# rl_energy_board.net
KiCad netlist of a schematic drawn in EAGLE
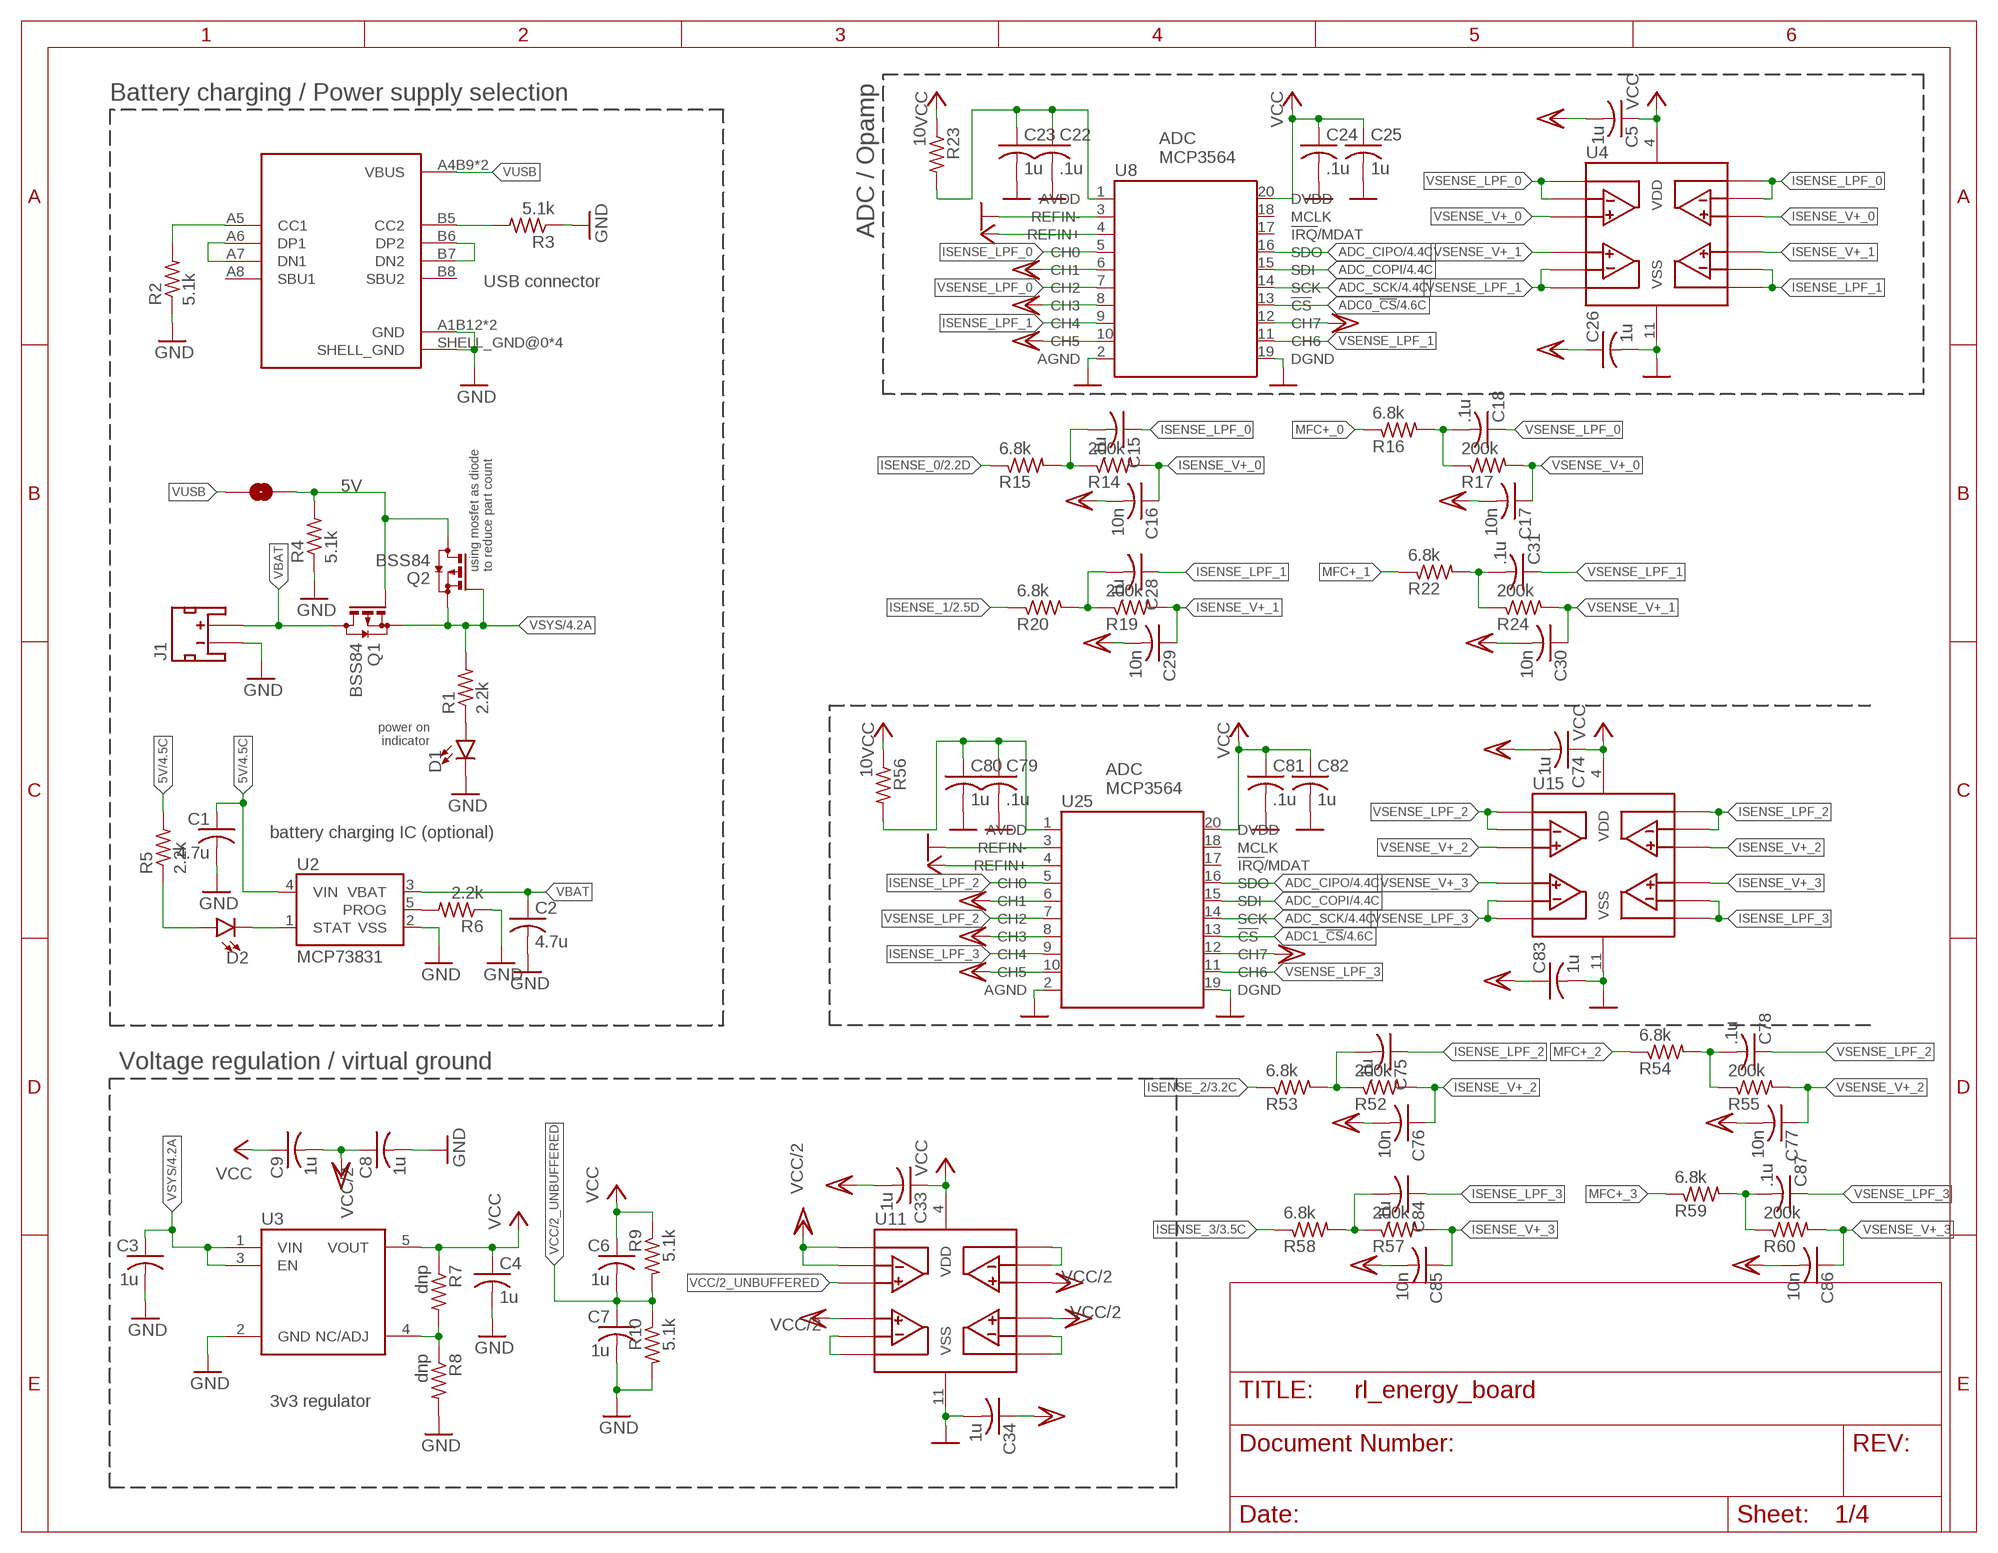
[diagram p0: schematic, sheet 1]
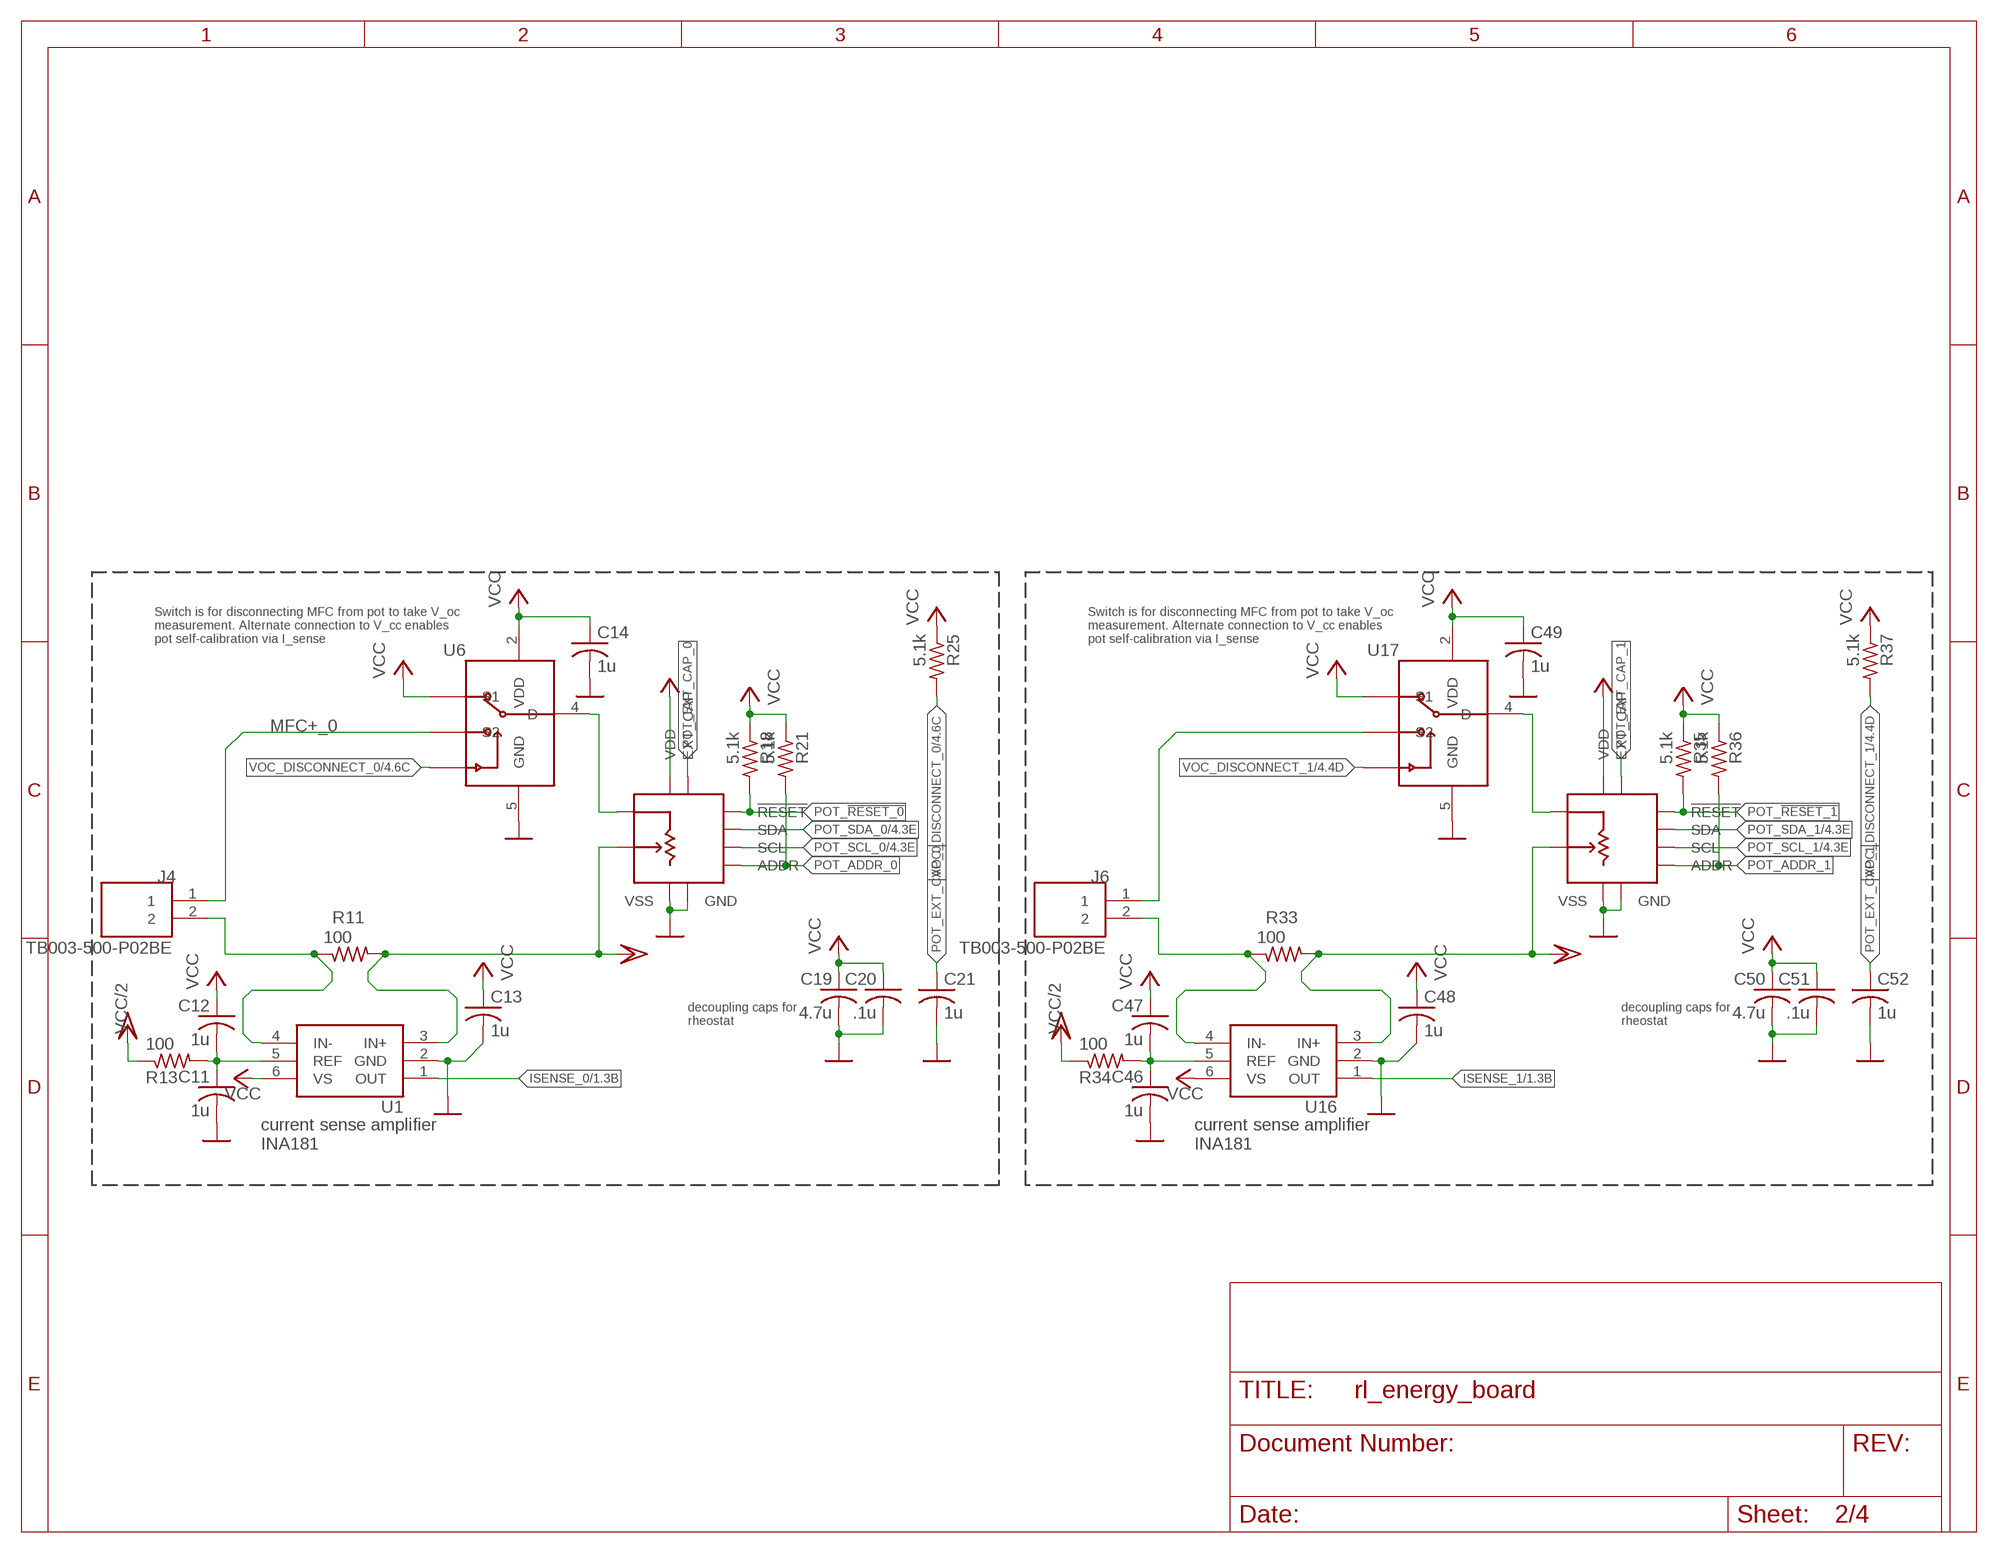
[diagram p1: schematic, sheet 2]
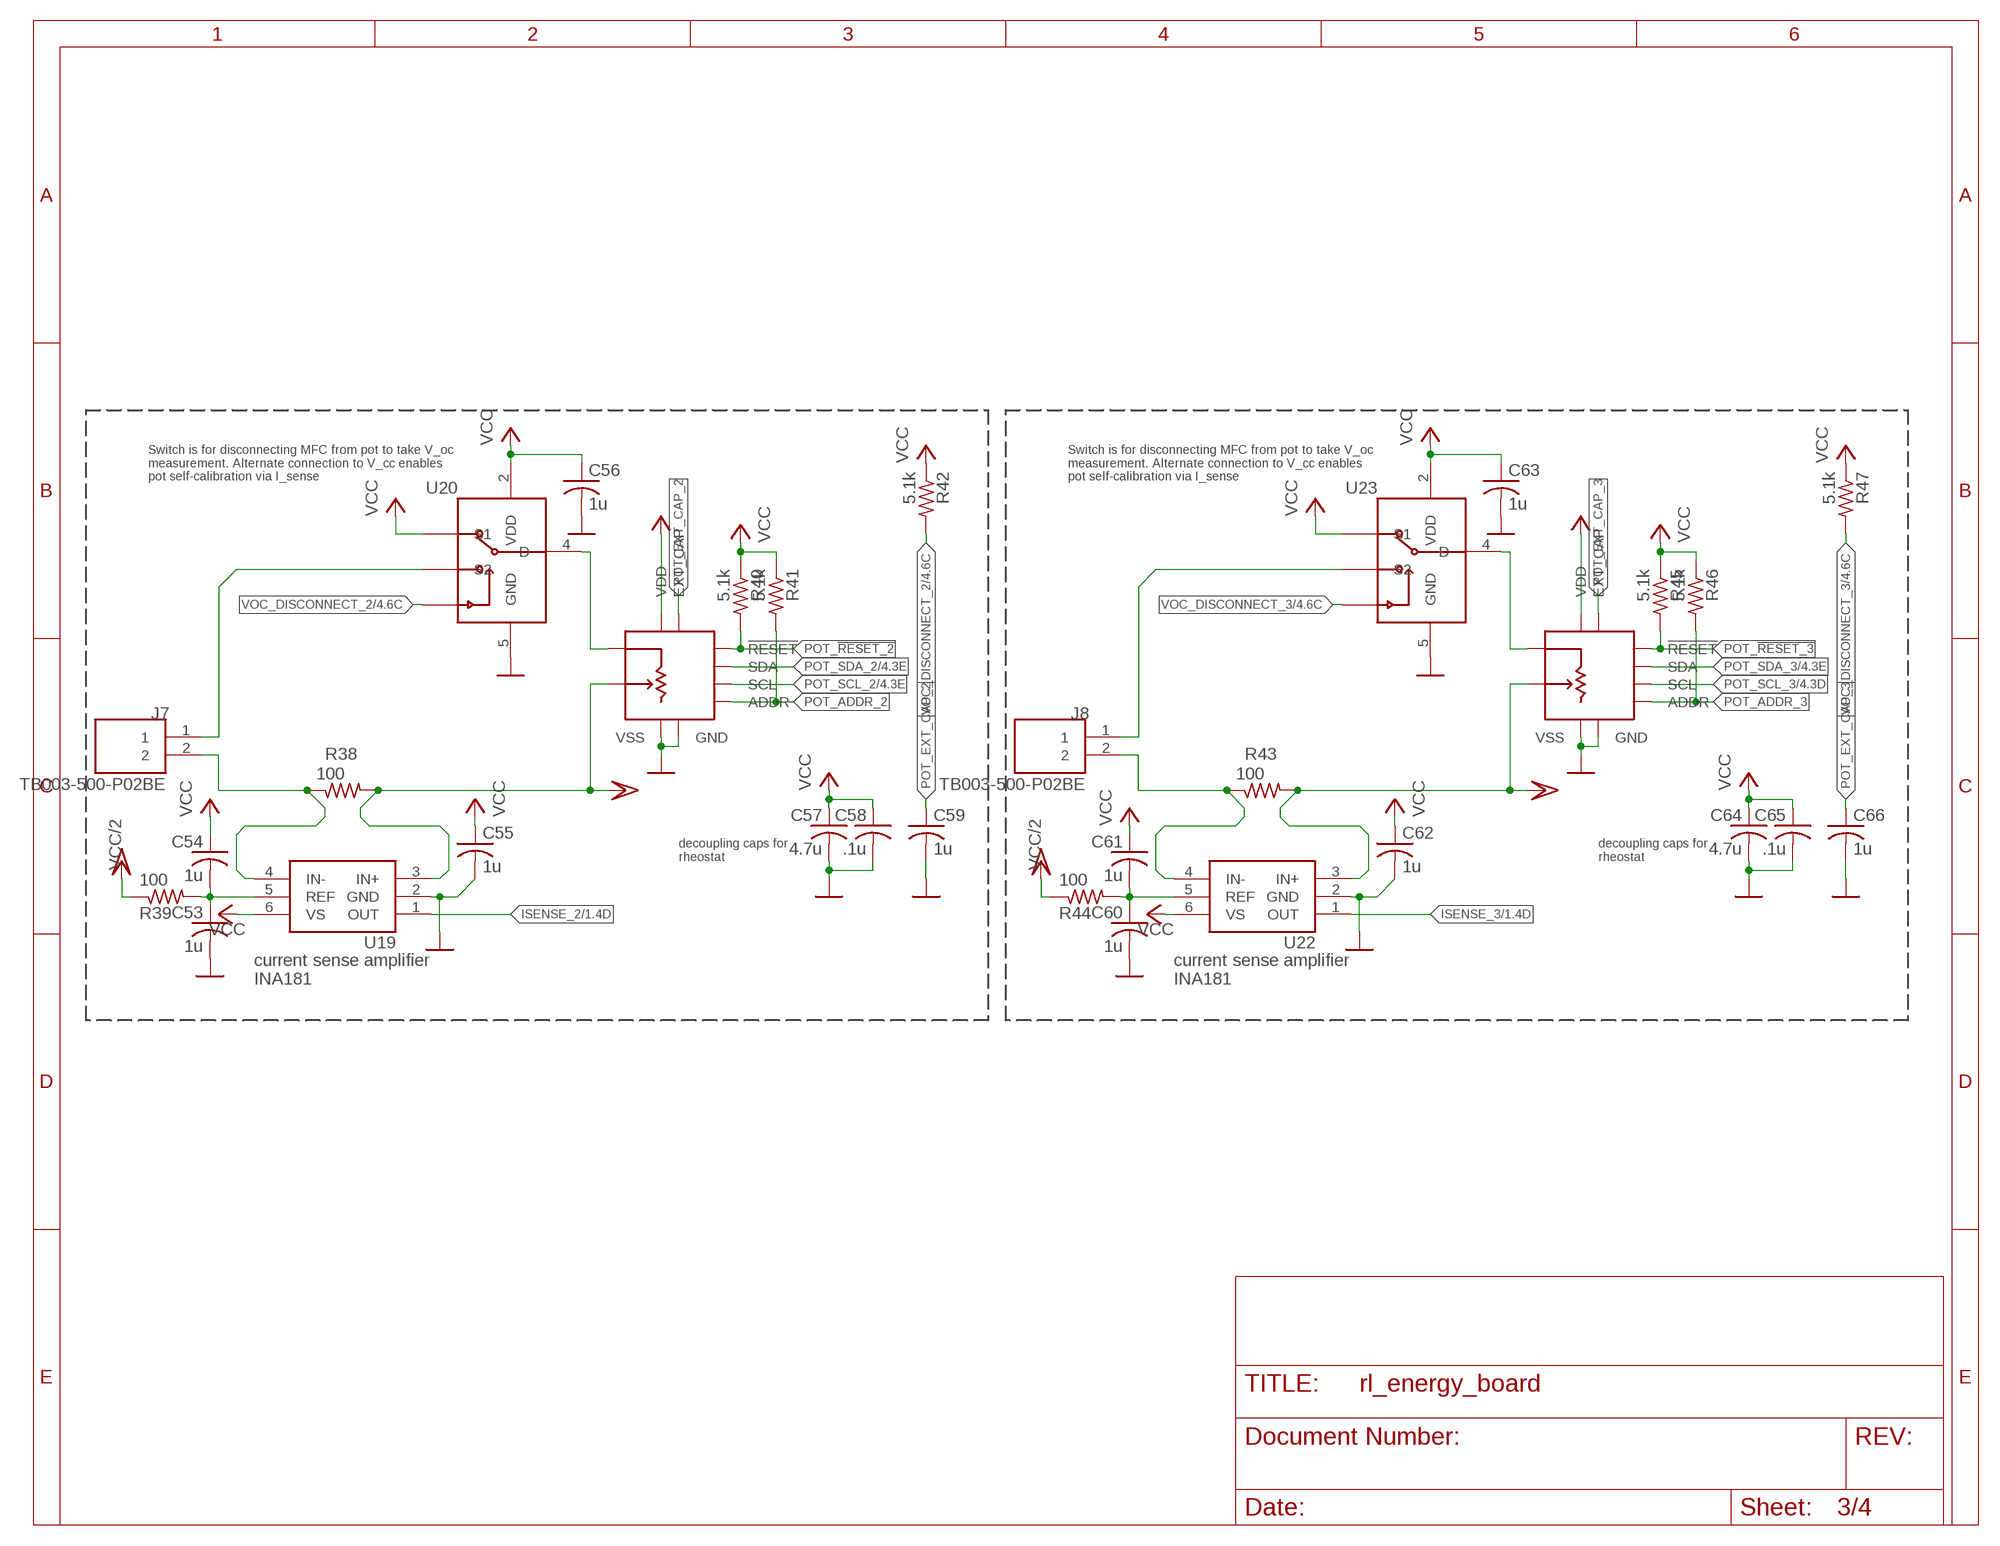
[diagram p2: schematic, sheet 3]
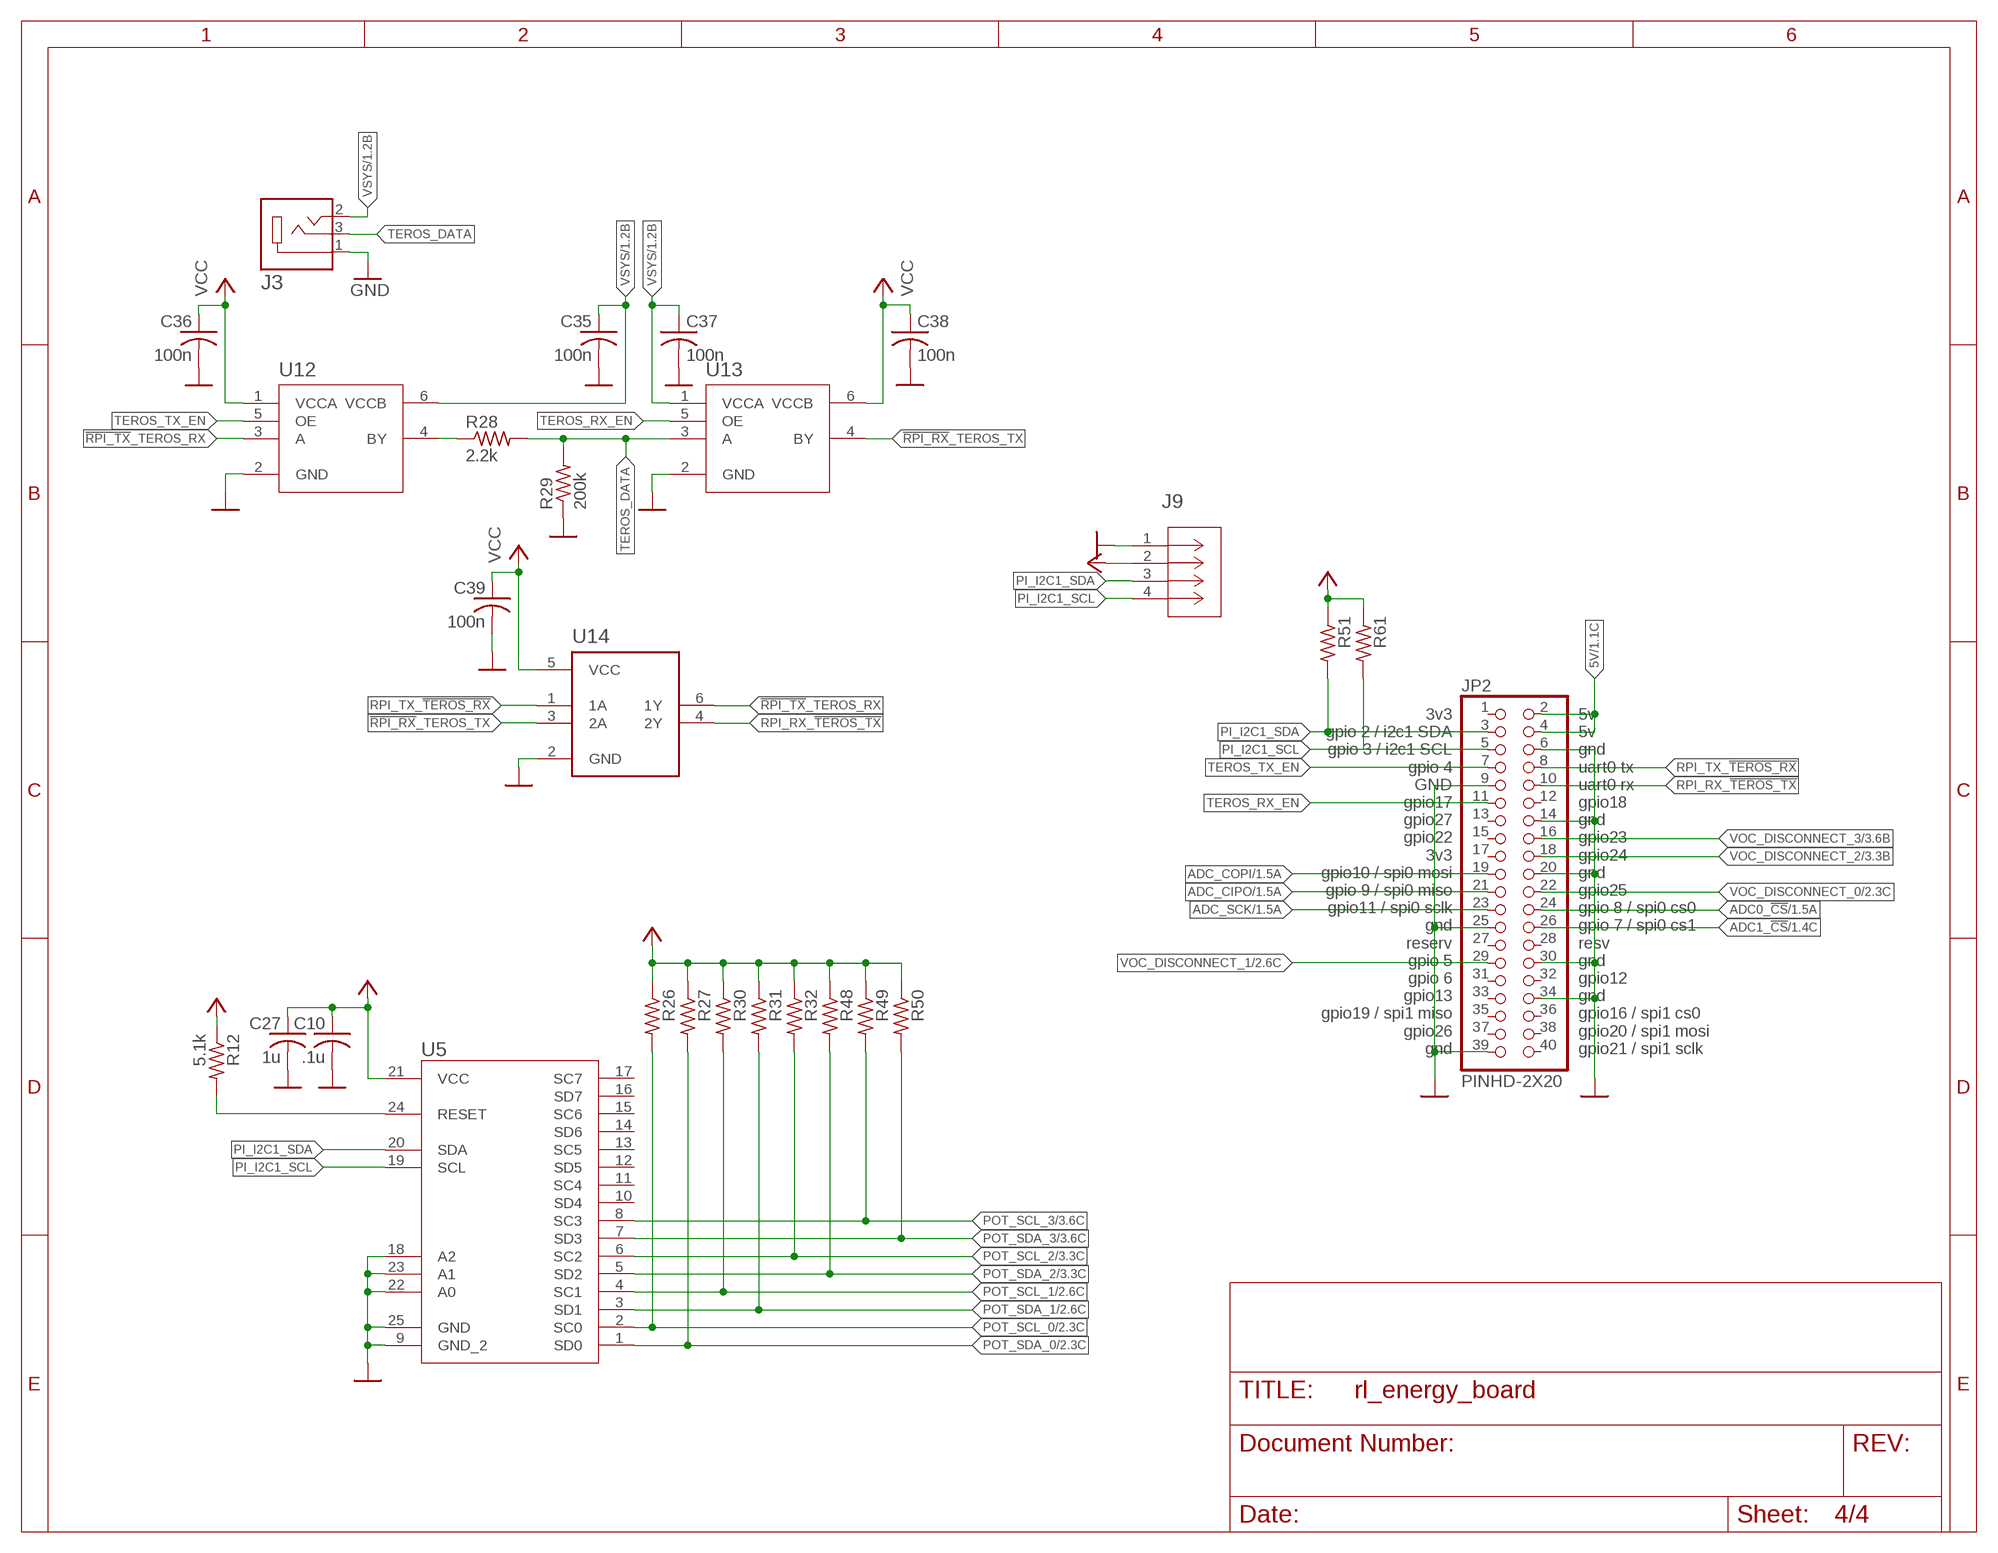
[diagram p3: schematic, sheet 4]

(export (version "E")
  (design (tool "Eeschema 10.0.6"))
  (components
    (comp (ref "C11")
      (value "1u")
      (footprint "eagle-import:C0402")
      (fields (field (name "MFR") "Samsung Electro-Mechanics"))
      (libsource (lib "eagle-import") (part "C-USC0402"))
    )
    (comp (ref "C12")
      (value "1u")
      (footprint "eagle-import:C0402")
      (fields (field (name "MFR") "Samsung Electro-Mechanics"))
      (libsource (lib "eagle-import") (part "C-USC0402"))
    )
    (comp (ref "C13")
      (value "1u")
      (footprint "eagle-import:C0402")
      (fields (field (name "MFR") "Samsung Electro-Mechanics"))
      (libsource (lib "eagle-import") (part "C-USC0402"))
    )
    (comp (ref "C14")
      (value "1u")
      (footprint "eagle-import:C0402")
      (fields (field (name "MFR") "Samsung Electro-Mechanics"))
      (libsource (lib "eagle-import") (part "C-USC0402"))
    )
    (comp (ref "C19")
      (value "4.7u")
      (footprint "eagle-import:C0603")
      (fields (field (name "MFR") "Samsung Electro-Mechanics"))
      (libsource (lib "eagle-import") (part "C-USC0603"))
    )
    (comp (ref "C20")
      (value ".1u")
      (footprint "eagle-import:C0402")
      (fields (field (name "MFR") "Samsung Electro-Mechanics"))
      (libsource (lib "eagle-import") (part "C-USC0402"))
    )
    (comp (ref "C21")
      (value "1u")
      (footprint "eagle-import:C0402")
      (fields (field (name "MFR") "Samsung Electro-Mechanics"))
      (libsource (lib "eagle-import") (part "C-USC0402"))
    )
    (comp (ref "C46")
      (value "1u")
      (footprint "eagle-import:C0402")
      (fields (field (name "MFR") "Samsung Electro-Mechanics"))
      (libsource (lib "eagle-import") (part "C-USC0402"))
    )
    (comp (ref "C47")
      (value "1u")
      (footprint "eagle-import:C0402")
      (fields (field (name "MFR") "Samsung Electro-Mechanics"))
      (libsource (lib "eagle-import") (part "C-USC0402"))
    )
    (comp (ref "C48")
      (value "1u")
      (footprint "eagle-import:C0402")
      (fields (field (name "MFR") "Samsung Electro-Mechanics"))
      (libsource (lib "eagle-import") (part "C-USC0402"))
    )
    (comp (ref "C49")
      (value "1u")
      (footprint "eagle-import:C0402")
      (fields (field (name "MFR") "Samsung Electro-Mechanics"))
      (libsource (lib "eagle-import") (part "C-USC0402"))
    )
    (comp (ref "C50")
      (value "4.7u")
      (footprint "eagle-import:C0603")
      (fields (field (name "MFR") "Samsung Electro-Mechanics"))
      (libsource (lib "eagle-import") (part "C-USC0603"))
    )
    (comp (ref "C51")
      (value ".1u")
      (footprint "eagle-import:C0402")
      (fields (field (name "MFR") "Samsung Electro-Mechanics"))
      (libsource (lib "eagle-import") (part "C-USC0402"))
    )
    (comp (ref "C52")
      (value "1u")
      (footprint "eagle-import:C0402")
      (fields (field (name "MFR") "Samsung Electro-Mechanics"))
      (libsource (lib "eagle-import") (part "C-USC0402"))
    )
    (comp (ref "J4")
      (value "TB003-500-P02BE")
      (footprint "eagle-import:CUI_TB003-500-P02BE")
      (fields (field (name "MANUFACTURER") "CUI"))
      (libsource (lib "eagle-import") (part "TB003-500-P02BE"))
    )
    (comp (ref "J6")
      (value "TB003-500-P02BE")
      (footprint "eagle-import:CUI_TB003-500-P02BE")
      (fields (field (name "MANUFACTURER") "CUI"))
      (libsource (lib "eagle-import") (part "TB003-500-P02BE"))
    )
    (comp (ref "R11")
      (value "100")
      (footprint "eagle-import:R0603")
      (fields (field (name "MFR") "Stackpole Electronics Incorporated"))
      (libsource (lib "eagle-import") (part "R-US_R0603"))
    )
    (comp (ref "R13")
      (value "100")
      (footprint "eagle-import:R0402")
      (fields (field (name "MFR") "Yageo"))
      (libsource (lib "eagle-import") (part "R-US_R0402"))
    )
    (comp (ref "R18")
      (value "5.1k")
      (footprint "eagle-import:R0402")
      (fields (field (name "MFR") "Yageo"))
      (libsource (lib "eagle-import") (part "R-US_R0402"))
    )
    (comp (ref "R21")
      (value "5.1k")
      (footprint "eagle-import:R0402")
      (fields (field (name "MFR") "Yageo"))
      (libsource (lib "eagle-import") (part "R-US_R0402"))
    )
    (comp (ref "R25")
      (value "5.1k")
      (footprint "eagle-import:R0402")
      (fields (field (name "MFR") "Yageo"))
      (libsource (lib "eagle-import") (part "R-US_R0402"))
    )
    (comp (ref "R33")
      (value "100")
      (footprint "eagle-import:R0603")
      (fields (field (name "MFR") "Stackpole Electronics Incorporated"))
      (libsource (lib "eagle-import") (part "R-US_R0603"))
    )
    (comp (ref "R34")
      (value "100")
      (footprint "eagle-import:R0402")
      (fields (field (name "MFR") "Yageo"))
      (libsource (lib "eagle-import") (part "R-US_R0402"))
    )
    (comp (ref "R35")
      (value "5.1k")
      (footprint "eagle-import:R0402")
      (fields (field (name "MFR") "Yageo"))
      (libsource (lib "eagle-import") (part "R-US_R0402"))
    )
    (comp (ref "R36")
      (value "5.1k")
      (footprint "eagle-import:R0402")
      (fields (field (name "MFR") "Yageo"))
      (libsource (lib "eagle-import") (part "R-US_R0402"))
    )
    (comp (ref "R37")
      (value "5.1k")
      (footprint "eagle-import:R0402")
      (fields (field (name "MFR") "Yageo"))
      (libsource (lib "eagle-import") (part "R-US_R0402"))
    )
    (comp (ref "U1")
      (value "INA181")
      (footprint "eagle-import:SOT95P280X145-6N")
      (fields (field (name "MFR") "Texas Instruments"))
      (libsource (lib "eagle-import") (part "INA181"))
    )
    (comp (ref "U6")
      (value "TMUX1247")
      (footprint "eagle-import:SOT65P210X110-6N")
      (fields (field (name "MFR") "Texas Instruments"))
      (libsource (lib "eagle-import") (part "TMUX1247"))
    )
    (comp (ref "U7")
      (value "AD5272BRMZ-XXX")
      (footprint "eagle-import:SOP50P490X95-10N")
      (fields (field (name "MFR") "Analog Devices"))
      (libsource (lib "eagle-import") (part "AD5272BRMZ-XXX"))
    )
    (comp (ref "U16")
      (value "INA181")
      (footprint "eagle-import:SOT95P280X145-6N")
      (fields (field (name "MFR") "Texas Instruments"))
      (libsource (lib "eagle-import") (part "INA181"))
    )
    (comp (ref "U17")
      (value "TMUX1247")
      (footprint "eagle-import:SOT65P210X110-6N")
      (fields (field (name "MFR") "Texas Instruments"))
      (libsource (lib "eagle-import") (part "TMUX1247"))
    )
    (comp (ref "U18")
      (value "AD5272BRMZ-XXX")
      (footprint "eagle-import:SOP50P490X95-10N")
      (fields (field (name "MFR") "Analog Devices"))
      (libsource (lib "eagle-import") (part "AD5272BRMZ-XXX"))
    )
    (comp (ref "C53")
      (value "1u")
      (footprint "eagle-import:C0402")
      (fields (field (name "MFR") "Samsung Electro-Mechanics"))
      (libsource (lib "eagle-import") (part "C-USC0402"))
    )
    (comp (ref "C54")
      (value "1u")
      (footprint "eagle-import:C0402")
      (fields (field (name "MFR") "Samsung Electro-Mechanics"))
      (libsource (lib "eagle-import") (part "C-USC0402"))
    )
    (comp (ref "C55")
      (value "1u")
      (footprint "eagle-import:C0402")
      (fields (field (name "MFR") "Samsung Electro-Mechanics"))
      (libsource (lib "eagle-import") (part "C-USC0402"))
    )
    (comp (ref "C56")
      (value "1u")
      (footprint "eagle-import:C0402")
      (fields (field (name "MFR") "Samsung Electro-Mechanics"))
      (libsource (lib "eagle-import") (part "C-USC0402"))
    )
    (comp (ref "C57")
      (value "4.7u")
      (footprint "eagle-import:C0603")
      (fields (field (name "MFR") "Samsung Electro-Mechanics"))
      (libsource (lib "eagle-import") (part "C-USC0603"))
    )
    (comp (ref "C58")
      (value ".1u")
      (footprint "eagle-import:C0402")
      (fields (field (name "MFR") "Samsung Electro-Mechanics"))
      (libsource (lib "eagle-import") (part "C-USC0402"))
    )
    (comp (ref "C59")
      (value "1u")
      (footprint "eagle-import:C0402")
      (fields (field (name "MFR") "Samsung Electro-Mechanics"))
      (libsource (lib "eagle-import") (part "C-USC0402"))
    )
    (comp (ref "C60")
      (value "1u")
      (footprint "eagle-import:C0402")
      (fields (field (name "MFR") "Samsung Electro-Mechanics"))
      (libsource (lib "eagle-import") (part "C-USC0402"))
    )
    (comp (ref "C61")
      (value "1u")
      (footprint "eagle-import:C0402")
      (fields (field (name "MFR") "Samsung Electro-Mechanics"))
      (libsource (lib "eagle-import") (part "C-USC0402"))
    )
    (comp (ref "C62")
      (value "1u")
      (footprint "eagle-import:C0402")
      (fields (field (name "MFR") "Samsung Electro-Mechanics"))
      (libsource (lib "eagle-import") (part "C-USC0402"))
    )
    (comp (ref "C63")
      (value "1u")
      (footprint "eagle-import:C0402")
      (fields (field (name "MFR") "Samsung Electro-Mechanics"))
      (libsource (lib "eagle-import") (part "C-USC0402"))
    )
    (comp (ref "C64")
      (value "4.7u")
      (footprint "eagle-import:C0603")
      (fields (field (name "MFR") "Samsung Electro-Mechanics"))
      (libsource (lib "eagle-import") (part "C-USC0603"))
    )
    (comp (ref "C65")
      (value ".1u")
      (footprint "eagle-import:C0402")
      (fields (field (name "MFR") "Samsung Electro-Mechanics"))
      (libsource (lib "eagle-import") (part "C-USC0402"))
    )
    (comp (ref "C66")
      (value "1u")
      (footprint "eagle-import:C0402")
      (fields (field (name "MFR") "Samsung Electro-Mechanics"))
      (libsource (lib "eagle-import") (part "C-USC0402"))
    )
    (comp (ref "J7")
      (value "TB003-500-P02BE")
      (footprint "eagle-import:CUI_TB003-500-P02BE")
      (fields (field (name "MANUFACTURER") "CUI"))
      (libsource (lib "eagle-import") (part "TB003-500-P02BE"))
    )
    (comp (ref "J8")
      (value "TB003-500-P02BE")
      (footprint "eagle-import:CUI_TB003-500-P02BE")
      (fields (field (name "MANUFACTURER") "CUI"))
      (libsource (lib "eagle-import") (part "TB003-500-P02BE"))
    )
    (comp (ref "R38")
      (value "100")
      (footprint "eagle-import:R0603")
      (fields (field (name "MFR") "Stackpole Electronics Incorporated"))
      (libsource (lib "eagle-import") (part "R-US_R0603"))
    )
    (comp (ref "R39")
      (value "100")
      (footprint "eagle-import:R0402")
      (fields (field (name "MFR") "Yageo"))
      (libsource (lib "eagle-import") (part "R-US_R0402"))
    )
    (comp (ref "R40")
      (value "5.1k")
      (footprint "eagle-import:R0402")
      (fields (field (name "MFR") "Yageo"))
      (libsource (lib "eagle-import") (part "R-US_R0402"))
    )
    (comp (ref "R41")
      (value "5.1k")
      (footprint "eagle-import:R0402")
      (fields (field (name "MFR") "Yageo"))
      (libsource (lib "eagle-import") (part "R-US_R0402"))
    )
    (comp (ref "R42")
      (value "5.1k")
      (footprint "eagle-import:R0402")
      (fields (field (name "MFR") "Yageo"))
      (libsource (lib "eagle-import") (part "R-US_R0402"))
    )
    (comp (ref "R43")
      (value "100")
      (footprint "eagle-import:R0603")
      (fields (field (name "MFR") "Stackpole Electronics Incorporated"))
      (libsource (lib "eagle-import") (part "R-US_R0603"))
    )
    (comp (ref "R44")
      (value "100")
      (footprint "eagle-import:R0402")
      (fields (field (name "MFR") "Yageo"))
      (libsource (lib "eagle-import") (part "R-US_R0402"))
    )
    (comp (ref "R45")
      (value "5.1k")
      (footprint "eagle-import:R0402")
      (fields (field (name "MFR") "Yageo"))
      (libsource (lib "eagle-import") (part "R-US_R0402"))
    )
    (comp (ref "R46")
      (value "5.1k")
      (footprint "eagle-import:R0402")
      (fields (field (name "MFR") "Yageo"))
      (libsource (lib "eagle-import") (part "R-US_R0402"))
    )
    (comp (ref "R47")
      (value "5.1k")
      (footprint "eagle-import:R0402")
      (fields (field (name "MFR") "Yageo"))
      (libsource (lib "eagle-import") (part "R-US_R0402"))
    )
    (comp (ref "U19")
      (value "INA181")
      (footprint "eagle-import:SOT95P280X145-6N")
      (fields (field (name "MFR") "Texas Instruments"))
      (libsource (lib "eagle-import") (part "INA181"))
    )
    (comp (ref "U20")
      (value "TMUX1247")
      (footprint "eagle-import:SOT65P210X110-6N")
      (fields (field (name "MFR") "Texas Instruments"))
      (libsource (lib "eagle-import") (part "TMUX1247"))
    )
    (comp (ref "U21")
      (value "AD5272BRMZ-XXX")
      (footprint "eagle-import:SOP50P490X95-10N")
      (fields (field (name "MFR") "Analog Devices"))
      (libsource (lib "eagle-import") (part "AD5272BRMZ-XXX"))
    )
    (comp (ref "U22")
      (value "INA181")
      (footprint "eagle-import:SOT95P280X145-6N")
      (fields (field (name "MFR") "Texas Instruments"))
      (libsource (lib "eagle-import") (part "INA181"))
    )
    (comp (ref "U23")
      (value "TMUX1247")
      (footprint "eagle-import:SOT65P210X110-6N")
      (fields (field (name "MFR") "Texas Instruments"))
      (libsource (lib "eagle-import") (part "TMUX1247"))
    )
    (comp (ref "U24")
      (value "AD5272BRMZ-XXX")
      (footprint "eagle-import:SOP50P490X95-10N")
      (fields (field (name "MFR") "Analog Devices"))
      (libsource (lib "eagle-import") (part "AD5272BRMZ-XXX"))
    )
    (comp (ref "C10")
      (value ".1u")
      (footprint "eagle-import:C0402")
      (fields (field (name "MFR") "Samsung Electro-Mechanics"))
      (libsource (lib "eagle-import") (part "C-USC0402"))
    )
    (comp (ref "C27")
      (value "1u")
      (footprint "eagle-import:C0402")
      (fields (field (name "MFR") "Samsung Electro-Mechanics"))
      (libsource (lib "eagle-import") (part "C-USC0402"))
    )
    (comp (ref "C35")
      (value "100n")
      (footprint "eagle-import:C0402")
      (libsource (lib "eagle-import") (part "C-USC0402"))
    )
    (comp (ref "C36")
      (value "100n")
      (footprint "eagle-import:C0402")
      (libsource (lib "eagle-import") (part "C-USC0402"))
    )
    (comp (ref "C37")
      (value "100n")
      (footprint "eagle-import:C0402")
      (libsource (lib "eagle-import") (part "C-USC0402"))
    )
    (comp (ref "C38")
      (value "100n")
      (footprint "eagle-import:C0402")
      (libsource (lib "eagle-import") (part "C-USC0402"))
    )
    (comp (ref "C39")
      (value "100n")
      (footprint "eagle-import:C0402")
      (libsource (lib "eagle-import") (part "C-USC0402"))
    )
    (comp (ref "J3")
      (value "SJ-3523-SMT-TR")
      (footprint "eagle-import:CUI_SJ-3523-SMT-TR")
      (fields (field (name "MF") "CUI Inc"))
      (libsource (lib "eagle-import") (part "SJ-3523-SMT-TR"))
    )
    (comp (ref "J9")
      (value "SM04B-SRSS-TB")
      (footprint "eagle-import:CONN_SM04B-SRSS-TB_JST")
      (fields (field (name "COPYRIGHT") "Copyright (C) 2024 Ultra Librarian. All rights reserved."))
      (libsource (lib "eagle-import") (part "SM04B-SRSS-TB"))
    )
    (comp (ref "JP2")
      (value "PINHD-2X20")
      (footprint "eagle-import:2X20")
      (libsource (lib "eagle-import") (part "PINHD-2X20"))
    )
    (comp (ref "R12")
      (value "5.1k")
      (footprint "eagle-import:R0402")
      (fields (field (name "MFR") "Yageo"))
      (libsource (lib "eagle-import") (part "R-US_R0402"))
    )
    (comp (ref "R26")
      (value "5.1k")
      (footprint "eagle-import:R0402")
      (fields (field (name "MFR") "Yageo"))
      (libsource (lib "eagle-import") (part "R-US_R0402"))
    )
    (comp (ref "R27")
      (value "5.1k")
      (footprint "eagle-import:R0402")
      (fields (field (name "MFR") "Yageo"))
      (libsource (lib "eagle-import") (part "R-US_R0402"))
    )
    (comp (ref "R28")
      (value "2.2k")
      (footprint "eagle-import:R0402")
      (libsource (lib "eagle-import") (part "R-US_R0402"))
    )
    (comp (ref "R29")
      (value "200k")
      (footprint "eagle-import:R0402")
      (libsource (lib "eagle-import") (part "R-US_R0402"))
    )
    (comp (ref "R30")
      (value "5.1k")
      (footprint "eagle-import:R0402")
      (fields (field (name "MFR") "Yageo"))
      (libsource (lib "eagle-import") (part "R-US_R0402"))
    )
    (comp (ref "R31")
      (value "5.1k")
      (footprint "eagle-import:R0402")
      (fields (field (name "MFR") "Yageo"))
      (libsource (lib "eagle-import") (part "R-US_R0402"))
    )
    (comp (ref "R32")
      (value "5.1k")
      (footprint "eagle-import:R0402")
      (fields (field (name "MFR") "Yageo"))
      (libsource (lib "eagle-import") (part "R-US_R0402"))
    )
    (comp (ref "R48")
      (value "5.1k")
      (footprint "eagle-import:R0402")
      (fields (field (name "MFR") "Yageo"))
      (libsource (lib "eagle-import") (part "R-US_R0402"))
    )
    (comp (ref "R49")
      (value "5.1k")
      (footprint "eagle-import:R0402")
      (fields (field (name "MFR") "Yageo"))
      (libsource (lib "eagle-import") (part "R-US_R0402"))
    )
    (comp (ref "R50")
      (value "5.1k")
      (footprint "eagle-import:R0402")
      (fields (field (name "MFR") "Yageo"))
      (libsource (lib "eagle-import") (part "R-US_R0402"))
    )
    (comp (ref "R51")
      (value "5.1k")
      (footprint "eagle-import:R0402")
      (fields (field (name "MFR") "Yageo"))
      (libsource (lib "eagle-import") (part "R-US_R0402"))
    )
    (comp (ref "R61")
      (value "5.1k")
      (footprint "eagle-import:R0402")
      (fields (field (name "MFR") "Yageo"))
      (libsource (lib "eagle-import") (part "R-US_R0402"))
    )
    (comp (ref "U5")
      (value "TCA9548ARGERQ1")
      (footprint "eagle-import:QFN_GERQ1_TEX")
      (fields (field (name "COPYRIGHT") "Copyright (C) 2024 Ultra Librarian. All rights reserved."))
      (libsource (lib "eagle-import") (part "TCA9548ARGERQ1"))
    )
    (comp (ref "U12")
      (value "TXU0101QDCKRQ1")
      (footprint "eagle-import:SOT_101QDCKRQ1_TEX")
      (fields (field (name "COPYRIGHT") "Copyright (C) 2024 Ultra Librarian. All rights reserved."))
      (libsource (lib "eagle-import") (part "TXU0101QDCKRQ1"))
    )
    (comp (ref "U13")
      (value "TXU0101QDCKRQ1")
      (footprint "eagle-import:SOT_101QDCKRQ1_TEX")
      (fields (field (name "COPYRIGHT") "Copyright (C) 2024 Ultra Librarian. All rights reserved."))
      (libsource (lib "eagle-import") (part "TXU0101QDCKRQ1"))
    )
    (comp (ref "U14")
      (value "SN74LVC2G14DCKR")
      (footprint "eagle-import:SOT65P210X110-6N")
      (libsource (lib "eagle-import") (part "SN74LVC2G14DCKR"))
    )
    (comp (ref "C1")
      (value "4.7u")
      (footprint "eagle-import:C0603")
      (fields (field (name "MFR") "Samsung Electro-Mechanics"))
      (libsource (lib "eagle-import") (part "C-USC0603"))
    )
    (comp (ref "C2")
      (value "4.7u")
      (footprint "eagle-import:C0603")
      (fields (field (name "MFR") "Samsung Electro-Mechanics"))
      (libsource (lib "eagle-import") (part "C-USC0603"))
    )
    (comp (ref "C3")
      (value "1u")
      (footprint "eagle-import:C0402")
      (fields (field (name "MFR") "Samsung Electro-Mechanics"))
      (libsource (lib "eagle-import") (part "C-USC0402"))
    )
    (comp (ref "C4")
      (value "1u")
      (footprint "eagle-import:C0402")
      (fields (field (name "MFR") "Samsung Electro-Mechanics"))
      (libsource (lib "eagle-import") (part "C-USC0402"))
    )
    (comp (ref "C5")
      (value "1u")
      (footprint "eagle-import:C0402")
      (fields (field (name "MFR") "Samsung Electro-Mechanics"))
      (libsource (lib "eagle-import") (part "C-USC0402"))
    )
    (comp (ref "C6")
      (value "1u")
      (footprint "eagle-import:C0402")
      (fields (field (name "MFR") "Samsung Electro-Mechanics"))
      (libsource (lib "eagle-import") (part "C-USC0402"))
    )
    (comp (ref "C7")
      (value "1u")
      (footprint "eagle-import:C0402")
      (fields (field (name "MFR") "Samsung Electro-Mechanics"))
      (libsource (lib "eagle-import") (part "C-USC0402"))
    )
    (comp (ref "C8")
      (value "1u")
      (footprint "eagle-import:C0402")
      (fields (field (name "MFR") "Samsung Electro-Mechanics"))
      (libsource (lib "eagle-import") (part "C-USC0402"))
    )
    (comp (ref "C9")
      (value "1u")
      (footprint "eagle-import:C0402")
      (fields (field (name "MFR") "Samsung Electro-Mechanics"))
      (libsource (lib "eagle-import") (part "C-USC0402"))
    )
    (comp (ref "C15")
      (value ".1u")
      (footprint "eagle-import:C0402")
      (fields (field (name "MFR") "Samsung Electro-Mechanics"))
      (libsource (lib "eagle-import") (part "C-USC0402"))
    )
    (comp (ref "C16")
      (value "10n")
      (footprint "eagle-import:C0402")
      (fields (field (name "MFR") "Samsung Electro-Mechanics"))
      (libsource (lib "eagle-import") (part "C-USC0402"))
    )
    (comp (ref "C17")
      (value "10n")
      (footprint "eagle-import:C0402")
      (fields (field (name "MFR") "Samsung Electro-Mechanics"))
      (libsource (lib "eagle-import") (part "C-USC0402"))
    )
    (comp (ref "C18")
      (value ".1u")
      (footprint "eagle-import:C0402")
      (fields (field (name "MFR") "Samsung Electro-Mechanics"))
      (libsource (lib "eagle-import") (part "C-USC0402"))
    )
    (comp (ref "C22")
      (value ".1u")
      (footprint "eagle-import:C0402")
      (fields (field (name "MFR") "Samsung Electro-Mechanics"))
      (libsource (lib "eagle-import") (part "C-USC0402"))
    )
    (comp (ref "C23")
      (value "1u")
      (footprint "eagle-import:C0402")
      (fields (field (name "MFR") "Samsung Electro-Mechanics"))
      (libsource (lib "eagle-import") (part "C-USC0402"))
    )
    (comp (ref "C24")
      (value ".1u")
      (footprint "eagle-import:C0402")
      (fields (field (name "MFR") "Samsung Electro-Mechanics"))
      (libsource (lib "eagle-import") (part "C-USC0402"))
    )
    (comp (ref "C25")
      (value "1u")
      (footprint "eagle-import:C0402")
      (fields (field (name "MFR") "Samsung Electro-Mechanics"))
      (libsource (lib "eagle-import") (part "C-USC0402"))
    )
    (comp (ref "C26")
      (value "1u")
      (footprint "eagle-import:C0402")
      (fields (field (name "MFR") "Samsung Electro-Mechanics"))
      (libsource (lib "eagle-import") (part "C-USC0402"))
    )
    (comp (ref "C28")
      (value ".1u")
      (footprint "eagle-import:C0402")
      (fields (field (name "MFR") "Samsung Electro-Mechanics"))
      (libsource (lib "eagle-import") (part "C-USC0402"))
    )
    (comp (ref "C29")
      (value "10n")
      (footprint "eagle-import:C0402")
      (fields (field (name "MFR") "Samsung Electro-Mechanics"))
      (libsource (lib "eagle-import") (part "C-USC0402"))
    )
    (comp (ref "C30")
      (value "10n")
      (footprint "eagle-import:C0402")
      (fields (field (name "MFR") "Samsung Electro-Mechanics"))
      (libsource (lib "eagle-import") (part "C-USC0402"))
    )
    (comp (ref "C31")
      (value ".1u")
      (footprint "eagle-import:C0402")
      (fields (field (name "MFR") "Samsung Electro-Mechanics"))
      (libsource (lib "eagle-import") (part "C-USC0402"))
    )
    (comp (ref "C33")
      (value "1u")
      (footprint "eagle-import:C0402")
      (fields (field (name "MFR") "Samsung Electro-Mechanics"))
      (libsource (lib "eagle-import") (part "C-USC0402"))
    )
    (comp (ref "C34")
      (value "1u")
      (footprint "eagle-import:C0402")
      (fields (field (name "MFR") "Samsung Electro-Mechanics"))
      (libsource (lib "eagle-import") (part "C-USC0402"))
    )
    (comp (ref "C74")
      (value "1u")
      (footprint "eagle-import:C0402")
      (fields (field (name "MFR") "Samsung Electro-Mechanics"))
      (libsource (lib "eagle-import") (part "C-USC0402"))
    )
    (comp (ref "C75")
      (value ".1u")
      (footprint "eagle-import:C0402")
      (fields (field (name "MFR") "Samsung Electro-Mechanics"))
      (libsource (lib "eagle-import") (part "C-USC0402"))
    )
    (comp (ref "C76")
      (value "10n")
      (footprint "eagle-import:C0402")
      (fields (field (name "MFR") "Samsung Electro-Mechanics"))
      (libsource (lib "eagle-import") (part "C-USC0402"))
    )
    (comp (ref "C77")
      (value "10n")
      (footprint "eagle-import:C0402")
      (fields (field (name "MFR") "Samsung Electro-Mechanics"))
      (libsource (lib "eagle-import") (part "C-USC0402"))
    )
    (comp (ref "C78")
      (value ".1u")
      (footprint "eagle-import:C0402")
      (fields (field (name "MFR") "Samsung Electro-Mechanics"))
      (libsource (lib "eagle-import") (part "C-USC0402"))
    )
    (comp (ref "C79")
      (value ".1u")
      (footprint "eagle-import:C0402")
      (fields (field (name "MFR") "Samsung Electro-Mechanics"))
      (libsource (lib "eagle-import") (part "C-USC0402"))
    )
    (comp (ref "C80")
      (value "1u")
      (footprint "eagle-import:C0402")
      (fields (field (name "MFR") "Samsung Electro-Mechanics"))
      (libsource (lib "eagle-import") (part "C-USC0402"))
    )
    (comp (ref "C81")
      (value ".1u")
      (footprint "eagle-import:C0402")
      (fields (field (name "MFR") "Samsung Electro-Mechanics"))
      (libsource (lib "eagle-import") (part "C-USC0402"))
    )
    (comp (ref "C82")
      (value "1u")
      (footprint "eagle-import:C0402")
      (fields (field (name "MFR") "Samsung Electro-Mechanics"))
      (libsource (lib "eagle-import") (part "C-USC0402"))
    )
    (comp (ref "C83")
      (value "1u")
      (footprint "eagle-import:C0402")
      (fields (field (name "MFR") "Samsung Electro-Mechanics"))
      (libsource (lib "eagle-import") (part "C-USC0402"))
    )
    (comp (ref "C84")
      (value ".1u")
      (footprint "eagle-import:C0402")
      (fields (field (name "MFR") "Samsung Electro-Mechanics"))
      (libsource (lib "eagle-import") (part "C-USC0402"))
    )
    (comp (ref "C85")
      (value "10n")
      (footprint "eagle-import:C0402")
      (fields (field (name "MFR") "Samsung Electro-Mechanics"))
      (libsource (lib "eagle-import") (part "C-USC0402"))
    )
    (comp (ref "C86")
      (value "10n")
      (footprint "eagle-import:C0402")
      (fields (field (name "MFR") "Samsung Electro-Mechanics"))
      (libsource (lib "eagle-import") (part "C-USC0402"))
    )
    (comp (ref "C87")
      (value ".1u")
      (footprint "eagle-import:C0402")
      (fields (field (name "MFR") "Samsung Electro-Mechanics"))
      (libsource (lib "eagle-import") (part "C-USC0402"))
    )
    (comp (ref "D1")
      (value "LED0603")
      (footprint "eagle-import:LED-0603")
      (fields (field (name "MFR") "Lite-On Incorporated"))
      (libsource (lib "eagle-import") (part "LED0603"))
    )
    (comp (ref "D2")
      (value "LED0603")
      (footprint "eagle-import:LED-0603")
      (fields (field (name "MFR") "Lite-On Incorporated"))
      (libsource (lib "eagle-import") (part "LED0603"))
    )
    (comp (ref "J1")
      (value "JST_2MM_MALE")
      (footprint "eagle-import:JST-2-SMD")
      (fields (field (name "MFR") "JST"))
      (libsource (lib "eagle-import") (part "JST_2MM_MALE"))
    )
    (comp (ref "J2")
      (value "USB4105")
      (footprint "eagle-import:USB4105")
      (fields (field (name "MFR") "GCT"))
      (libsource (lib "eagle-import") (part "USB4105"))
    )
    (comp (ref "JP1")
      (value "JUMPER-SMT_2_NO_NO-SILK")
      (footprint "eagle-import:SMT-JUMPER_2_NO_NO-SILK")
      (libsource (lib "eagle-import") (part "JUMPER-SMT_2_NO_NO-SILK"))
    )
    (comp (ref "Q1")
      (value "BSS84")
      (footprint "eagle-import:SOT23")
      (fields (field (name "MFR") "Taiwan Semiconductor Corporation"))
      (libsource (lib "eagle-import") (part "BSS84"))
    )
    (comp (ref "Q2")
      (value "BSS84")
      (footprint "eagle-import:SOT23")
      (fields (field (name "MFR") "Taiwan Semiconductor Corporation"))
      (libsource (lib "eagle-import") (part "BSS84"))
    )
    (comp (ref "R1")
      (value "2.2k")
      (footprint "eagle-import:R0402")
      (fields (field (name "MFR") "Yageo"))
      (libsource (lib "eagle-import") (part "resistor_348_R-US_R0402"))
    )
    (comp (ref "R2")
      (value "5.1k")
      (footprint "eagle-import:R0402")
      (fields (field (name "MFR") "Yageo"))
      (libsource (lib "eagle-import") (part "resistor_348_R-US_R0402"))
    )
    (comp (ref "R3")
      (value "5.1k")
      (footprint "eagle-import:R0402")
      (fields (field (name "MFR") "Yageo"))
      (libsource (lib "eagle-import") (part "resistor_348_R-US_R0402"))
    )
    (comp (ref "R4")
      (value "5.1k")
      (footprint "eagle-import:R0402")
      (fields (field (name "MFR") "Yageo"))
      (libsource (lib "eagle-import") (part "resistor_348_R-US_R0402"))
    )
    (comp (ref "R5")
      (value "2.2k")
      (footprint "eagle-import:R0402")
      (fields (field (name "MFR") "Yageo"))
      (libsource (lib "eagle-import") (part "resistor_348_R-US_R0402"))
    )
    (comp (ref "R6")
      (value "2.2k")
      (footprint "eagle-import:R0402")
      (fields (field (name "MFR") "Yageo"))
      (libsource (lib "eagle-import") (part "resistor_348_R-US_R0402"))
    )
    (comp (ref "R7")
      (value "dnp")
      (footprint "eagle-import:R0402")
      (libsource (lib "eagle-import") (part "resistor_348_R-US_R0402"))
    )
    (comp (ref "R8")
      (value "dnp")
      (footprint "eagle-import:R0402")
      (libsource (lib "eagle-import") (part "resistor_348_R-US_R0402"))
    )
    (comp (ref "R9")
      (value "5.1k")
      (footprint "eagle-import:R0402")
      (fields (field (name "MFR") "Yageo"))
      (libsource (lib "eagle-import") (part "resistor_348_R-US_R0402"))
    )
    (comp (ref "R10")
      (value "5.1k")
      (footprint "eagle-import:R0402")
      (fields (field (name "MFR") "Yageo"))
      (libsource (lib "eagle-import") (part "resistor_348_R-US_R0402"))
    )
    (comp (ref "R14")
      (value "200k")
      (footprint "eagle-import:R0402")
      (fields (field (name "MFR") "Yageo"))
      (libsource (lib "eagle-import") (part "R-US_R0402"))
    )
    (comp (ref "R15")
      (value "6.8k")
      (footprint "eagle-import:R0402")
      (fields (field (name "MFR") "Yageo"))
      (libsource (lib "eagle-import") (part "R-US_R0402"))
    )
    (comp (ref "R16")
      (value "6.8k")
      (footprint "eagle-import:R0402")
      (fields (field (name "MFR") "Yageo"))
      (libsource (lib "eagle-import") (part "R-US_R0402"))
    )
    (comp (ref "R17")
      (value "200k")
      (footprint "eagle-import:R0402")
      (fields (field (name "MFR") "Yageo"))
      (libsource (lib "eagle-import") (part "R-US_R0402"))
    )
    (comp (ref "R19")
      (value "200k")
      (footprint "eagle-import:R0402")
      (fields (field (name "MFR") "Yageo"))
      (libsource (lib "eagle-import") (part "R-US_R0402"))
    )
    (comp (ref "R20")
      (value "6.8k")
      (footprint "eagle-import:R0402")
      (fields (field (name "MFR") "Yageo"))
      (libsource (lib "eagle-import") (part "R-US_R0402"))
    )
    (comp (ref "R22")
      (value "6.8k")
      (footprint "eagle-import:R0402")
      (fields (field (name "MFR") "Yageo"))
      (libsource (lib "eagle-import") (part "R-US_R0402"))
    )
    (comp (ref "R23")
      (value "10")
      (footprint "eagle-import:R0402")
      (fields (field (name "MFR") "Stackpole Electronics Incorporated"))
      (libsource (lib "eagle-import") (part "R-US_R0402"))
    )
    (comp (ref "R24")
      (value "200k")
      (footprint "eagle-import:R0402")
      (fields (field (name "MFR") "Yageo"))
      (libsource (lib "eagle-import") (part "R-US_R0402"))
    )
    (comp (ref "R52")
      (value "200k")
      (footprint "eagle-import:R0402")
      (fields (field (name "MFR") "Yageo"))
      (libsource (lib "eagle-import") (part "R-US_R0402"))
    )
    (comp (ref "R53")
      (value "6.8k")
      (footprint "eagle-import:R0402")
      (fields (field (name "MFR") "Yageo"))
      (libsource (lib "eagle-import") (part "R-US_R0402"))
    )
    (comp (ref "R54")
      (value "6.8k")
      (footprint "eagle-import:R0402")
      (fields (field (name "MFR") "Yageo"))
      (libsource (lib "eagle-import") (part "R-US_R0402"))
    )
    (comp (ref "R55")
      (value "200k")
      (footprint "eagle-import:R0402")
      (fields (field (name "MFR") "Yageo"))
      (libsource (lib "eagle-import") (part "R-US_R0402"))
    )
    (comp (ref "R56")
      (value "10")
      (footprint "eagle-import:R0402")
      (fields (field (name "MFR") "Stackpole Electronics Incorporated"))
      (libsource (lib "eagle-import") (part "R-US_R0402"))
    )
    (comp (ref "R57")
      (value "200k")
      (footprint "eagle-import:R0402")
      (fields (field (name "MFR") "Yageo"))
      (libsource (lib "eagle-import") (part "R-US_R0402"))
    )
    (comp (ref "R58")
      (value "6.8k")
      (footprint "eagle-import:R0402")
      (fields (field (name "MFR") "Yageo"))
      (libsource (lib "eagle-import") (part "R-US_R0402"))
    )
    (comp (ref "R59")
      (value "6.8k")
      (footprint "eagle-import:R0402")
      (fields (field (name "MFR") "Yageo"))
      (libsource (lib "eagle-import") (part "R-US_R0402"))
    )
    (comp (ref "R60")
      (value "200k")
      (footprint "eagle-import:R0402")
      (fields (field (name "MFR") "Yageo"))
      (libsource (lib "eagle-import") (part "R-US_R0402"))
    )
    (comp (ref "U2")
      (value "MCP73831")
      (footprint "eagle-import:SOT23-5")
      (fields (field (name "MFR") "Microchip Technology"))
      (libsource (lib "eagle-import") (part "MCP73831"))
    )
    (comp (ref "U3")
      (value "AP7366")
      (footprint "eagle-import:SOT95P285X130-5N")
      (fields (field (name "MFR") "Diodes Incorporated"))
      (libsource (lib "eagle-import") (part "AP7366"))
    )
    (comp (ref "U4")
      (value "MCP6074")
      (footprint "eagle-import:SOP65P640X120-14N")
      (fields (field (name "MFR") "Microchip Technology"))
      (libsource (lib "eagle-import") (part "MCP6074"))
    )
    (comp (ref "U8")
      (value "MCP3564")
      (footprint "eagle-import:SOP65P640X120-20N")
      (fields (field (name "MFR") "Microchip Technology"))
      (libsource (lib "eagle-import") (part "MCP3564"))
    )
    (comp (ref "U11")
      (value "MCP6074")
      (footprint "eagle-import:SOP65P640X120-14N")
      (fields (field (name "MFR") "Microchip Technology"))
      (libsource (lib "eagle-import") (part "MCP6074"))
    )
    (comp (ref "U15")
      (value "MCP6074")
      (footprint "eagle-import:SOP65P640X120-14N")
      (fields (field (name "MFR") "Microchip Technology"))
      (libsource (lib "eagle-import") (part "MCP6074"))
    )
    (comp (ref "U25")
      (value "MCP3564")
      (footprint "eagle-import:SOP65P640X120-20N")
      (fields (field (name "MFR") "Microchip Technology"))
      (libsource (lib "eagle-import") (part "MCP3564"))
    )
  )
  (nets
    (net (code "1") (name "5V") (class "Default")
      (node (ref "C1") (pin "1") (pinfunction "1_1") (pintype "passive"))
      (node (ref "JP1") (pin "1") (pinfunction "1_1") (pintype "passive"))
      (node (ref "JP2") (pin "2") (pinfunction "2_2") (pintype "passive"))
      (node (ref "JP2") (pin "4") (pinfunction "4_4") (pintype "passive"))
      (node (ref "Q1") (pin "1") (pinfunction "G_1") (pintype "passive"))
      (node (ref "Q2") (pin "3") (pinfunction "D_3") (pintype "passive"))
      (node (ref "R4") (pin "2") (pinfunction "2_2") (pintype "passive"))
      (node (ref "R5") (pin "2") (pinfunction "2_2") (pintype "passive"))
      (node (ref "U2") (pin "4") (pinfunction "VIN_4") (pintype "power_in"))
    )
    (net (code "2") (name "ADC0_~{CS}") (class "Default")
      (node (ref "JP2") (pin "24") (pinfunction "24_24") (pintype "passive"))
      (node (ref "U8") (pin "13") (pinfunction "~{CS}_13") (pintype "bidirectional"))
    )
    (net (code "3") (name "ADC1_~{CS}") (class "Default")
      (node (ref "JP2") (pin "26") (pinfunction "26_26") (pintype "passive"))
      (node (ref "U25") (pin "13") (pinfunction "~{CS}_13") (pintype "bidirectional"))
    )
    (net (code "4") (name "ADC_CIPO") (class "Default")
      (node (ref "JP2") (pin "21") (pinfunction "21_21") (pintype "passive"))
      (node (ref "U25") (pin "16") (pinfunction "SDO_16") (pintype "bidirectional"))
      (node (ref "U8") (pin "16") (pinfunction "SDO_16") (pintype "bidirectional"))
    )
    (net (code "5") (name "ADC_COPI") (class "Default")
      (node (ref "JP2") (pin "19") (pinfunction "19_19") (pintype "passive"))
      (node (ref "U25") (pin "15") (pinfunction "SDI_15") (pintype "bidirectional"))
      (node (ref "U8") (pin "15") (pinfunction "SDI_15") (pintype "bidirectional"))
    )
    (net (code "6") (name "ADC_SCK") (class "Default")
      (node (ref "JP2") (pin "23") (pinfunction "23_23") (pintype "passive"))
      (node (ref "U25") (pin "14") (pinfunction "SCK_14") (pintype "bidirectional"))
      (node (ref "U8") (pin "14") (pinfunction "SCK_14") (pintype "bidirectional"))
    )
    (net (code "7") (name "GND") (class "Default")
      (node (ref "C1") (pin "2") (pinfunction "2_2") (pintype "passive"))
      (node (ref "C10") (pin "2") (pinfunction "2_2") (pintype "passive"))
      (node (ref "C11") (pin "2") (pinfunction "2_2") (pintype "passive"))
      (node (ref "C13") (pin "2") (pinfunction "2_2") (pintype "passive"))
      (node (ref "C14") (pin "2") (pinfunction "2_2") (pintype "passive"))
      (node (ref "C19") (pin "2") (pinfunction "2_2") (pintype "passive"))
      (node (ref "C2") (pin "2") (pinfunction "2_2") (pintype "passive"))
      (node (ref "C20") (pin "2") (pinfunction "2_2") (pintype "passive"))
      (node (ref "C21") (pin "2") (pinfunction "2_2") (pintype "passive"))
      (node (ref "C22") (pin "2") (pinfunction "2_2") (pintype "passive"))
      (node (ref "C23") (pin "2") (pinfunction "2_2") (pintype "passive"))
      (node (ref "C24") (pin "2") (pinfunction "2_2") (pintype "passive"))
      (node (ref "C25") (pin "2") (pinfunction "2_2") (pintype "passive"))
      (node (ref "C26") (pin "2") (pinfunction "2_2") (pintype "passive"))
      (node (ref "C27") (pin "2") (pinfunction "2_2") (pintype "passive"))
      (node (ref "C3") (pin "2") (pinfunction "2_2") (pintype "passive"))
      (node (ref "C34") (pin "2") (pinfunction "2_2") (pintype "passive"))
      (node (ref "C35") (pin "2") (pinfunction "2_2") (pintype "passive"))
      (node (ref "C36") (pin "2") (pinfunction "2_2") (pintype "passive"))
      (node (ref "C37") (pin "2") (pinfunction "2_2") (pintype "passive"))
      (node (ref "C38") (pin "2") (pinfunction "2_2") (pintype "passive"))
      (node (ref "C39") (pin "2") (pinfunction "2_2") (pintype "passive"))
      (node (ref "C4") (pin "2") (pinfunction "2_2") (pintype "passive"))
      (node (ref "C46") (pin "2") (pinfunction "2_2") (pintype "passive"))
      (node (ref "C48") (pin "2") (pinfunction "2_2") (pintype "passive"))
      (node (ref "C49") (pin "2") (pinfunction "2_2") (pintype "passive"))
      (node (ref "C50") (pin "2") (pinfunction "2_2") (pintype "passive"))
      (node (ref "C51") (pin "2") (pinfunction "2_2") (pintype "passive"))
      (node (ref "C52") (pin "2") (pinfunction "2_2") (pintype "passive"))
      (node (ref "C53") (pin "2") (pinfunction "2_2") (pintype "passive"))
      (node (ref "C55") (pin "2") (pinfunction "2_2") (pintype "passive"))
      (node (ref "C56") (pin "2") (pinfunction "2_2") (pintype "passive"))
      (node (ref "C57") (pin "2") (pinfunction "2_2") (pintype "passive"))
      (node (ref "C58") (pin "2") (pinfunction "2_2") (pintype "passive"))
      (node (ref "C59") (pin "2") (pinfunction "2_2") (pintype "passive"))
      (node (ref "C60") (pin "2") (pinfunction "2_2") (pintype "passive"))
      (node (ref "C62") (pin "2") (pinfunction "2_2") (pintype "passive"))
      (node (ref "C63") (pin "2") (pinfunction "2_2") (pintype "passive"))
      (node (ref "C64") (pin "2") (pinfunction "2_2") (pintype "passive"))
      (node (ref "C65") (pin "2") (pinfunction "2_2") (pintype "passive"))
      (node (ref "C66") (pin "2") (pinfunction "2_2") (pintype "passive"))
      (node (ref "C7") (pin "2") (pinfunction "2_2") (pintype "passive"))
      (node (ref "C79") (pin "2") (pinfunction "2_2") (pintype "passive"))
      (node (ref "C8") (pin "2") (pinfunction "2_2") (pintype "passive"))
      (node (ref "C80") (pin "2") (pinfunction "2_2") (pintype "passive"))
      (node (ref "C81") (pin "2") (pinfunction "2_2") (pintype "passive"))
      (node (ref "C82") (pin "2") (pinfunction "2_2") (pintype "passive"))
      (node (ref "C83") (pin "2") (pinfunction "2_2") (pintype "passive"))
      (node (ref "D1") (pin "C") (pinfunction "C_C") (pintype "passive"))
      (node (ref "J1") (pin "1") (pinfunction "-_1") (pintype "bidirectional"))
      (node (ref "J2") (pin "A1B12") (pinfunction "GND_A1B12") (pintype "bidirectional"))
      (node (ref "J2") (pin "B1A12") (pinfunction "GND_B1A12") (pintype "bidirectional"))
      (node (ref "J2") (pin "SHELL_GND@0") (pinfunction "SHELL_GND_SHELL_GND@0") (pintype "bidirectional"))
      (node (ref "J2") (pin "SHELL_GND@1") (pinfunction "SHELL_GND_SHELL_GND@1") (pintype "bidirectional"))
      (node (ref "J2") (pin "SHELL_GND@2") (pinfunction "SHELL_GND_SHELL_GND@2") (pintype "bidirectional"))
      (node (ref "J2") (pin "SHELL_GND@3") (pinfunction "SHELL_GND_SHELL_GND@3") (pintype "bidirectional"))
      (node (ref "J3") (pin "1") (pinfunction "1_1") (pintype "passive"))
      (node (ref "J9") (pin "1") (pinfunction "1_1") (pintype "passive"))
      (node (ref "JP2") (pin "14") (pinfunction "14_14") (pintype "passive"))
      (node (ref "JP2") (pin "20") (pinfunction "20_20") (pintype "passive"))
      (node (ref "JP2") (pin "25") (pinfunction "25_25") (pintype "passive"))
      (node (ref "JP2") (pin "30") (pinfunction "30_30") (pintype "passive"))
      (node (ref "JP2") (pin "34") (pinfunction "34_34") (pintype "passive"))
      (node (ref "JP2") (pin "39") (pinfunction "39_39") (pintype "passive"))
      (node (ref "JP2") (pin "6") (pinfunction "6_6") (pintype "passive"))
      (node (ref "JP2") (pin "9") (pinfunction "9_9") (pintype "passive"))
      (node (ref "R10") (pin "2") (pinfunction "2_2") (pintype "passive"))
      (node (ref "R2") (pin "1") (pinfunction "1_1") (pintype "passive"))
      (node (ref "R29") (pin "1") (pinfunction "1_1") (pintype "passive"))
      (node (ref "R3") (pin "1") (pinfunction "1_1") (pintype "passive"))
      (node (ref "R4") (pin "1") (pinfunction "1_1") (pintype "passive"))
      (node (ref "R6") (pin "1") (pinfunction "1_1") (pintype "passive"))
      (node (ref "R8") (pin "2") (pinfunction "2_2") (pintype "passive"))
      (node (ref "U1") (pin "2") (pinfunction "GND_2") (pintype "bidirectional"))
      (node (ref "U11") (pin "11") (pinfunction "VSS_11") (pintype "bidirectional"))
      (node (ref "U12") (pin "2") (pinfunction "GND_2") (pintype "passive"))
      (node (ref "U13") (pin "2") (pinfunction "GND_2") (pintype "passive"))
      (node (ref "U14") (pin "2") (pinfunction "GND_2") (pintype "power_in"))
      (node (ref "U15") (pin "11") (pinfunction "VSS_11") (pintype "bidirectional"))
      (node (ref "U16") (pin "2") (pinfunction "GND_2") (pintype "bidirectional"))
      (node (ref "U17") (pin "5") (pinfunction "GND_5") (pintype "bidirectional"))
      (node (ref "U18") (pin "4") (pinfunction "VSS_4") (pintype "bidirectional"))
      (node (ref "U18") (pin "6") (pinfunction "GND_6") (pintype "bidirectional"))
      (node (ref "U19") (pin "2") (pinfunction "GND_2") (pintype "bidirectional"))
      (node (ref "U2") (pin "2") (pinfunction "VSS_2") (pintype "power_in"))
      (node (ref "U20") (pin "5") (pinfunction "GND_5") (pintype "bidirectional"))
      (node (ref "U21") (pin "4") (pinfunction "VSS_4") (pintype "bidirectional"))
      (node (ref "U21") (pin "6") (pinfunction "GND_6") (pintype "bidirectional"))
      (node (ref "U22") (pin "2") (pinfunction "GND_2") (pintype "bidirectional"))
      (node (ref "U23") (pin "5") (pinfunction "GND_5") (pintype "bidirectional"))
      (node (ref "U24") (pin "4") (pinfunction "VSS_4") (pintype "bidirectional"))
      (node (ref "U24") (pin "6") (pinfunction "GND_6") (pintype "bidirectional"))
      (node (ref "U25") (pin "19") (pinfunction "DGND_19") (pintype "bidirectional"))
      (node (ref "U25") (pin "2") (pinfunction "AGND_2") (pintype "bidirectional"))
      (node (ref "U25") (pin "3") (pinfunction "REFIN-_3") (pintype "bidirectional"))
      (node (ref "U3") (pin "2") (pinfunction "GND_2") (pintype "bidirectional"))
      (node (ref "U4") (pin "11") (pinfunction "VSS_11") (pintype "bidirectional"))
      (node (ref "U5") (pin "18") (pinfunction "A2_18") (pintype "bidirectional"))
      (node (ref "U5") (pin "22") (pinfunction "A0_22") (pintype "bidirectional"))
      (node (ref "U5") (pin "23") (pinfunction "A1_23") (pintype "bidirectional"))
      (node (ref "U5") (pin "25") (pinfunction "GND_25") (pintype "passive"))
      (node (ref "U5") (pin "9") (pinfunction "GND_2_9") (pintype "passive"))
      (node (ref "U6") (pin "5") (pinfunction "GND_5") (pintype "bidirectional"))
      (node (ref "U7") (pin "4") (pinfunction "VSS_4") (pintype "bidirectional"))
      (node (ref "U7") (pin "6") (pinfunction "GND_6") (pintype "bidirectional"))
      (node (ref "U8") (pin "19") (pinfunction "DGND_19") (pintype "bidirectional"))
      (node (ref "U8") (pin "2") (pinfunction "AGND_2") (pintype "bidirectional"))
      (node (ref "U8") (pin "3") (pinfunction "REFIN-_3") (pintype "bidirectional"))
    )
    (net (code "8") (name "ISENSE_0") (class "Default")
      (node (ref "R15") (pin "1") (pinfunction "1_1") (pintype "passive"))
      (node (ref "U1") (pin "1") (pinfunction "OUT_1") (pintype "bidirectional"))
    )
    (net (code "9") (name "ISENSE_1") (class "Default")
      (node (ref "R20") (pin "1") (pinfunction "1_1") (pintype "passive"))
      (node (ref "U16") (pin "1") (pinfunction "OUT_1") (pintype "bidirectional"))
    )
    (net (code "10") (name "ISENSE_2") (class "Default")
      (node (ref "R53") (pin "1") (pinfunction "1_1") (pintype "passive"))
      (node (ref "U19") (pin "1") (pinfunction "OUT_1") (pintype "bidirectional"))
    )
    (net (code "11") (name "ISENSE_3") (class "Default")
      (node (ref "R58") (pin "1") (pinfunction "1_1") (pintype "passive"))
      (node (ref "U22") (pin "1") (pinfunction "OUT_1") (pintype "bidirectional"))
    )
    (net (code "12") (name "ISENSE_LPF_0") (class "Default")
      (node (ref "C15") (pin "1") (pinfunction "1_1") (pintype "passive"))
      (node (ref "U4") (pin "13") (pinfunction "P$13_13") (pintype "bidirectional"))
      (node (ref "U4") (pin "14") (pinfunction "P$14_14") (pintype "bidirectional"))
      (node (ref "U8") (pin "5") (pinfunction "CH0_5") (pintype "bidirectional"))
    )
    (net (code "13") (name "ISENSE_LPF_1") (class "Default")
      (node (ref "C28") (pin "1") (pinfunction "1_1") (pintype "passive"))
      (node (ref "U4") (pin "8") (pinfunction "P$8_8") (pintype "bidirectional"))
      (node (ref "U4") (pin "9") (pinfunction "P$9_9") (pintype "bidirectional"))
      (node (ref "U8") (pin "9") (pinfunction "CH4_9") (pintype "bidirectional"))
    )
    (net (code "14") (name "ISENSE_LPF_2") (class "Default")
      (node (ref "C75") (pin "1") (pinfunction "1_1") (pintype "passive"))
      (node (ref "U15") (pin "13") (pinfunction "P$13_13") (pintype "bidirectional"))
      (node (ref "U15") (pin "14") (pinfunction "P$14_14") (pintype "bidirectional"))
      (node (ref "U25") (pin "5") (pinfunction "CH0_5") (pintype "bidirectional"))
    )
    (net (code "15") (name "ISENSE_LPF_3") (class "Default")
      (node (ref "C84") (pin "1") (pinfunction "1_1") (pintype "passive"))
      (node (ref "U15") (pin "8") (pinfunction "P$8_8") (pintype "bidirectional"))
      (node (ref "U15") (pin "9") (pinfunction "P$9_9") (pintype "bidirectional"))
      (node (ref "U25") (pin "9") (pinfunction "CH4_9") (pintype "bidirectional"))
    )
    (net (code "16") (name "ISENSE_V+_0") (class "Default")
      (node (ref "C16") (pin "1") (pinfunction "1_1") (pintype "passive"))
      (node (ref "R14") (pin "2") (pinfunction "2_2") (pintype "passive"))
      (node (ref "U4") (pin "12") (pinfunction "P$12_12") (pintype "bidirectional"))
    )
    (net (code "17") (name "ISENSE_V+_1") (class "Default")
      (node (ref "C29") (pin "1") (pinfunction "1_1") (pintype "passive"))
      (node (ref "R19") (pin "2") (pinfunction "2_2") (pintype "passive"))
      (node (ref "U4") (pin "10") (pinfunction "P$10_10") (pintype "bidirectional"))
    )
    (net (code "18") (name "ISENSE_V+_2") (class "Default")
      (node (ref "C76") (pin "1") (pinfunction "1_1") (pintype "passive"))
      (node (ref "R52") (pin "2") (pinfunction "2_2") (pintype "passive"))
      (node (ref "U15") (pin "12") (pinfunction "P$12_12") (pintype "bidirectional"))
    )
    (net (code "19") (name "ISENSE_V+_3") (class "Default")
      (node (ref "C85") (pin "1") (pinfunction "1_1") (pintype "passive"))
      (node (ref "R57") (pin "2") (pinfunction "2_2") (pintype "passive"))
      (node (ref "U15") (pin "10") (pinfunction "P$10_10") (pintype "bidirectional"))
    )
    (net (code "20") (name "MFC+_0") (class "Default")
      (node (ref "J4") (pin "1") (pinfunction "1_1") (pintype "passive"))
      (node (ref "R16") (pin "1") (pinfunction "1_1") (pintype "passive"))
      (node (ref "U6") (pin "1") (pinfunction "S2_1") (pintype "bidirectional"))
    )
    (net (code "21") (name "MFC+_1") (class "Default")
      (node (ref "J6") (pin "1") (pinfunction "1_1") (pintype "passive"))
      (node (ref "R22") (pin "1") (pinfunction "1_1") (pintype "passive"))
      (node (ref "U17") (pin "1") (pinfunction "S2_1") (pintype "bidirectional"))
    )
    (net (code "22") (name "MFC+_2") (class "Default")
      (node (ref "J7") (pin "1") (pinfunction "1_1") (pintype "passive"))
      (node (ref "R54") (pin "1") (pinfunction "1_1") (pintype "passive"))
      (node (ref "U20") (pin "1") (pinfunction "S2_1") (pintype "bidirectional"))
    )
    (net (code "23") (name "MFC+_3") (class "Default")
      (node (ref "J8") (pin "1") (pinfunction "1_1") (pintype "passive"))
      (node (ref "R59") (pin "1") (pinfunction "1_1") (pintype "passive"))
      (node (ref "U23") (pin "1") (pinfunction "S2_1") (pintype "bidirectional"))
    )
    (net (code "24") (name "N$35") (class "Default")
      (node (ref "C78") (pin "2") (pinfunction "2_2") (pintype "passive"))
      (node (ref "R54") (pin "2") (pinfunction "2_2") (pintype "passive"))
      (node (ref "R55") (pin "1") (pinfunction "1_1") (pintype "passive"))
    )
    (net (code "25") (name "Net-(C15-Pad2)") (class "Default")
      (node (ref "C15") (pin "2") (pinfunction "2_2") (pintype "passive"))
      (node (ref "R14") (pin "1") (pinfunction "1_1") (pintype "passive"))
      (node (ref "R15") (pin "2") (pinfunction "2_2") (pintype "passive"))
    )
    (net (code "26") (name "Net-(C18-Pad2)") (class "Default")
      (node (ref "C18") (pin "2") (pinfunction "2_2") (pintype "passive"))
      (node (ref "R16") (pin "2") (pinfunction "2_2") (pintype "passive"))
      (node (ref "R17") (pin "1") (pinfunction "1_1") (pintype "passive"))
    )
    (net (code "27") (name "Net-(C28-Pad2)") (class "Default")
      (node (ref "C28") (pin "2") (pinfunction "2_2") (pintype "passive"))
      (node (ref "R19") (pin "1") (pinfunction "1_1") (pintype "passive"))
      (node (ref "R20") (pin "2") (pinfunction "2_2") (pintype "passive"))
    )
    (net (code "28") (name "Net-(C31-Pad2)") (class "Default")
      (node (ref "C31") (pin "2") (pinfunction "2_2") (pintype "passive"))
      (node (ref "R22") (pin "2") (pinfunction "2_2") (pintype "passive"))
      (node (ref "R24") (pin "1") (pinfunction "1_1") (pintype "passive"))
    )
    (net (code "29") (name "Net-(C75-Pad2)") (class "Default")
      (node (ref "C75") (pin "2") (pinfunction "2_2") (pintype "passive"))
      (node (ref "R52") (pin "1") (pinfunction "1_1") (pintype "passive"))
      (node (ref "R53") (pin "2") (pinfunction "2_2") (pintype "passive"))
    )
    (net (code "30") (name "Net-(C84-Pad2)") (class "Default")
      (node (ref "C84") (pin "2") (pinfunction "2_2") (pintype "passive"))
      (node (ref "R57") (pin "1") (pinfunction "1_1") (pintype "passive"))
      (node (ref "R58") (pin "2") (pinfunction "2_2") (pintype "passive"))
    )
    (net (code "31") (name "Net-(C87-Pad2)") (class "Default")
      (node (ref "C87") (pin "2") (pinfunction "2_2") (pintype "passive"))
      (node (ref "R59") (pin "2") (pinfunction "2_2") (pintype "passive"))
      (node (ref "R60") (pin "1") (pinfunction "1_1") (pintype "passive"))
    )
    (net (code "32") (name "Net-(D1-PadA)") (class "Default")
      (node (ref "D1") (pin "A") (pinfunction "A_A") (pintype "passive"))
      (node (ref "R1") (pin "1") (pinfunction "1_1") (pintype "passive"))
    )
    (net (code "33") (name "Net-(D2-PadA)") (class "Default")
      (node (ref "D2") (pin "A") (pinfunction "A_A") (pintype "passive"))
      (node (ref "R5") (pin "1") (pinfunction "1_1") (pintype "passive"))
    )
    (net (code "34") (name "Net-(J2-CC1)") (class "Default")
      (node (ref "J2") (pin "A5") (pinfunction "CC1_A5") (pintype "bidirectional"))
      (node (ref "R2") (pin "2") (pinfunction "2_2") (pintype "passive"))
    )
    (net (code "35") (name "Net-(J2-CC2)") (class "Default")
      (node (ref "J2") (pin "B5") (pinfunction "CC2_B5") (pintype "bidirectional"))
      (node (ref "R3") (pin "2") (pinfunction "2_2") (pintype "passive"))
    )
    (net (code "36") (name "Net-(J2-DN1)") (class "Default")
      (node (ref "J2") (pin "A6") (pinfunction "DP1_A6") (pintype "bidirectional"))
      (node (ref "J2") (pin "A7") (pinfunction "DN1_A7") (pintype "bidirectional"))
    )
    (net (code "37") (name "Net-(J2-DN2)") (class "Default")
      (node (ref "J2") (pin "B6") (pinfunction "DP2_B6") (pintype "bidirectional"))
      (node (ref "J2") (pin "B7") (pinfunction "DN2_B7") (pintype "bidirectional"))
    )
    (net (code "38") (name "Net-(U1-IN-)") (class "Default")
      (node (ref "J4") (pin "2") (pinfunction "2_2") (pintype "passive"))
      (node (ref "R11") (pin "1") (pinfunction "1_1") (pintype "passive"))
      (node (ref "U1") (pin "4") (pinfunction "IN-_4") (pintype "bidirectional"))
    )
    (net (code "39") (name "Net-(U1-REF)") (class "Default")
      (node (ref "C11") (pin "1") (pinfunction "1_1") (pintype "passive"))
      (node (ref "C12") (pin "2") (pinfunction "2_2") (pintype "passive"))
      (node (ref "R13") (pin "2") (pinfunction "2_2") (pintype "passive"))
      (node (ref "U1") (pin "5") (pinfunction "REF_5") (pintype "bidirectional"))
    )
    (net (code "40") (name "Net-(U2-PROG)") (class "Default")
      (node (ref "R6") (pin "2") (pinfunction "2_2") (pintype "passive"))
      (node (ref "U2") (pin "5") (pinfunction "PROG_5") (pintype "input"))
    )
    (net (code "41") (name "Net-(U2-STAT)") (class "Default")
      (node (ref "D2") (pin "C") (pinfunction "C_C") (pintype "passive"))
      (node (ref "U2") (pin "1") (pinfunction "STAT_1") (pintype "output"))
    )
    (net (code "42") (name "Net-(U3-NC{slash}ADJ)") (class "Default")
      (node (ref "R7") (pin "2") (pinfunction "2_2") (pintype "passive"))
      (node (ref "R8") (pin "1") (pinfunction "1_1") (pintype "passive"))
      (node (ref "U3") (pin "4") (pinfunction "NC/ADJ_4") (pintype "bidirectional"))
    )
    (net (code "43") (name "Net-(U5-RESET)") (class "Default")
      (node (ref "R12") (pin "2") (pinfunction "2_2") (pintype "passive"))
      (node (ref "U5") (pin "24") (pinfunction "RESET_24") (pintype "passive"))
    )
    (net (code "44") (name "Net-(U6-D)") (class "Default")
      (node (ref "U6") (pin "4") (pinfunction "D_4") (pintype "bidirectional"))
      (node (ref "U7") (pin "2") (pinfunction "A_2") (pintype "bidirectional"))
    )
    (net (code "45") (name "Net-(U8-AVDD)") (class "Default")
      (node (ref "C22") (pin "1") (pinfunction "1_1") (pintype "passive"))
      (node (ref "C23") (pin "1") (pinfunction "1_1") (pintype "passive"))
      (node (ref "R23") (pin "2") (pinfunction "2_2") (pintype "passive"))
      (node (ref "U8") (pin "1") (pinfunction "AVDD_1") (pintype "bidirectional"))
    )
    (net (code "46") (name "Net-(U11-P$6)") (class "Default")
      (node (ref "U11") (pin "6") (pinfunction "P$6_6") (pintype "bidirectional"))
      (node (ref "U11") (pin "7") (pinfunction "P$7_7") (pintype "bidirectional"))
    )
    (net (code "47") (name "Net-(U11-P$8)") (class "Default")
      (node (ref "U11") (pin "8") (pinfunction "P$8_8") (pintype "bidirectional"))
      (node (ref "U11") (pin "9") (pinfunction "P$9_9") (pintype "bidirectional"))
    )
    (net (code "48") (name "Net-(U11-P$13)") (class "Default")
      (node (ref "U11") (pin "13") (pinfunction "P$13_13") (pintype "bidirectional"))
      (node (ref "U11") (pin "14") (pinfunction "P$14_14") (pintype "bidirectional"))
    )
    (net (code "49") (name "Net-(U12-BY)") (class "Default")
      (node (ref "R28") (pin "1") (pinfunction "1_1") (pintype "passive"))
      (node (ref "U12") (pin "4") (pinfunction "BY_4") (pintype "passive"))
    )
    (net (code "50") (name "Net-(U16-IN-)") (class "Default")
      (node (ref "J6") (pin "2") (pinfunction "2_2") (pintype "passive"))
      (node (ref "R33") (pin "1") (pinfunction "1_1") (pintype "passive"))
      (node (ref "U16") (pin "4") (pinfunction "IN-_4") (pintype "bidirectional"))
    )
    (net (code "51") (name "Net-(U16-REF)") (class "Default")
      (node (ref "C46") (pin "1") (pinfunction "1_1") (pintype "passive"))
      (node (ref "C47") (pin "2") (pinfunction "2_2") (pintype "passive"))
      (node (ref "R34") (pin "2") (pinfunction "2_2") (pintype "passive"))
      (node (ref "U16") (pin "5") (pinfunction "REF_5") (pintype "bidirectional"))
    )
    (net (code "52") (name "Net-(U17-D)") (class "Default")
      (node (ref "U17") (pin "4") (pinfunction "D_4") (pintype "bidirectional"))
      (node (ref "U18") (pin "2") (pinfunction "A_2") (pintype "bidirectional"))
    )
    (net (code "53") (name "Net-(U19-IN-)") (class "Default")
      (node (ref "J7") (pin "2") (pinfunction "2_2") (pintype "passive"))
      (node (ref "R38") (pin "1") (pinfunction "1_1") (pintype "passive"))
      (node (ref "U19") (pin "4") (pinfunction "IN-_4") (pintype "bidirectional"))
    )
    (net (code "54") (name "Net-(U19-REF)") (class "Default")
      (node (ref "C53") (pin "1") (pinfunction "1_1") (pintype "passive"))
      (node (ref "C54") (pin "2") (pinfunction "2_2") (pintype "passive"))
      (node (ref "R39") (pin "2") (pinfunction "2_2") (pintype "passive"))
      (node (ref "U19") (pin "5") (pinfunction "REF_5") (pintype "bidirectional"))
    )
    (net (code "55") (name "Net-(U20-D)") (class "Default")
      (node (ref "U20") (pin "4") (pinfunction "D_4") (pintype "bidirectional"))
      (node (ref "U21") (pin "2") (pinfunction "A_2") (pintype "bidirectional"))
    )
    (net (code "56") (name "Net-(U22-IN-)") (class "Default")
      (node (ref "J8") (pin "2") (pinfunction "2_2") (pintype "passive"))
      (node (ref "R43") (pin "1") (pinfunction "1_1") (pintype "passive"))
      (node (ref "U22") (pin "4") (pinfunction "IN-_4") (pintype "bidirectional"))
    )
    (net (code "57") (name "Net-(U22-REF)") (class "Default")
      (node (ref "C60") (pin "1") (pinfunction "1_1") (pintype "passive"))
      (node (ref "C61") (pin "2") (pinfunction "2_2") (pintype "passive"))
      (node (ref "R44") (pin "2") (pinfunction "2_2") (pintype "passive"))
      (node (ref "U22") (pin "5") (pinfunction "REF_5") (pintype "bidirectional"))
    )
    (net (code "58") (name "Net-(U23-D)") (class "Default")
      (node (ref "U23") (pin "4") (pinfunction "D_4") (pintype "bidirectional"))
      (node (ref "U24") (pin "2") (pinfunction "A_2") (pintype "bidirectional"))
    )
    (net (code "59") (name "Net-(U25-AVDD)") (class "Default")
      (node (ref "C79") (pin "1") (pinfunction "1_1") (pintype "passive"))
      (node (ref "C80") (pin "1") (pinfunction "1_1") (pintype "passive"))
      (node (ref "R56") (pin "2") (pinfunction "2_2") (pintype "passive"))
      (node (ref "U25") (pin "1") (pinfunction "AVDD_1") (pintype "bidirectional"))
    )
    (net (code "60") (name "PI_I2C1_SCL") (class "Default")
      (node (ref "J9") (pin "4") (pinfunction "4_4") (pintype "passive"))
      (node (ref "JP2") (pin "5") (pinfunction "5_5") (pintype "passive"))
      (node (ref "R61") (pin "2") (pinfunction "2_2") (pintype "passive"))
      (node (ref "U5") (pin "19") (pinfunction "SCL_19") (pintype "passive"))
    )
    (net (code "61") (name "PI_I2C1_SDA") (class "Default")
      (node (ref "J9") (pin "3") (pinfunction "3_3") (pintype "passive"))
      (node (ref "JP2") (pin "3") (pinfunction "3_3") (pintype "passive"))
      (node (ref "R51") (pin "2") (pinfunction "2_2") (pintype "passive"))
      (node (ref "U5") (pin "20") (pinfunction "SDA_20") (pintype "passive"))
    )
    (net (code "62") (name "POT_ADDR_0") (class "Default")
      (node (ref "R21") (pin "2") (pinfunction "2_2") (pintype "passive"))
      (node (ref "U7") (pin "10") (pinfunction "ADDR_10") (pintype "bidirectional"))
    )
    (net (code "63") (name "POT_ADDR_1") (class "Default")
      (node (ref "R36") (pin "2") (pinfunction "2_2") (pintype "passive"))
      (node (ref "U18") (pin "10") (pinfunction "ADDR_10") (pintype "bidirectional"))
    )
    (net (code "64") (name "POT_ADDR_2") (class "Default")
      (node (ref "R41") (pin "2") (pinfunction "2_2") (pintype "passive"))
      (node (ref "U21") (pin "10") (pinfunction "ADDR_10") (pintype "bidirectional"))
    )
    (net (code "65") (name "POT_ADDR_3") (class "Default")
      (node (ref "R46") (pin "2") (pinfunction "2_2") (pintype "passive"))
      (node (ref "U24") (pin "10") (pinfunction "ADDR_10") (pintype "bidirectional"))
    )
    (net (code "66") (name "POT_EXT_CAP_0") (class "Default")
      (node (ref "C21") (pin "1") (pinfunction "1_1") (pintype "passive"))
      (node (ref "U7") (pin "5") (pinfunction "EXT_CAP_5") (pintype "bidirectional"))
    )
    (net (code "67") (name "POT_EXT_CAP_1") (class "Default")
      (node (ref "C52") (pin "1") (pinfunction "1_1") (pintype "passive"))
      (node (ref "U18") (pin "5") (pinfunction "EXT_CAP_5") (pintype "bidirectional"))
    )
    (net (code "68") (name "POT_EXT_CAP_2") (class "Default")
      (node (ref "C59") (pin "1") (pinfunction "1_1") (pintype "passive"))
      (node (ref "U21") (pin "5") (pinfunction "EXT_CAP_5") (pintype "bidirectional"))
    )
    (net (code "69") (name "POT_EXT_CAP_3") (class "Default")
      (node (ref "C66") (pin "1") (pinfunction "1_1") (pintype "passive"))
      (node (ref "U24") (pin "5") (pinfunction "EXT_CAP_5") (pintype "bidirectional"))
    )
    (net (code "70") (name "POT_SCL_0") (class "Default")
      (node (ref "R26") (pin "2") (pinfunction "2_2") (pintype "passive"))
      (node (ref "U5") (pin "2") (pinfunction "SC0_2") (pintype "bidirectional"))
      (node (ref "U7") (pin "9") (pinfunction "SCL_9") (pintype "bidirectional"))
    )
    (net (code "71") (name "POT_SCL_1") (class "Default")
      (node (ref "R30") (pin "2") (pinfunction "2_2") (pintype "passive"))
      (node (ref "U18") (pin "9") (pinfunction "SCL_9") (pintype "bidirectional"))
      (node (ref "U5") (pin "4") (pinfunction "SC1_4") (pintype "bidirectional"))
    )
    (net (code "72") (name "POT_SCL_2") (class "Default")
      (node (ref "R32") (pin "2") (pinfunction "2_2") (pintype "passive"))
      (node (ref "U21") (pin "9") (pinfunction "SCL_9") (pintype "bidirectional"))
      (node (ref "U5") (pin "6") (pinfunction "SC2_6") (pintype "bidirectional"))
    )
    (net (code "73") (name "POT_SCL_3") (class "Default")
      (node (ref "R49") (pin "2") (pinfunction "2_2") (pintype "passive"))
      (node (ref "U24") (pin "9") (pinfunction "SCL_9") (pintype "bidirectional"))
      (node (ref "U5") (pin "8") (pinfunction "SC3_8") (pintype "bidirectional"))
    )
    (net (code "74") (name "POT_SDA_0") (class "Default")
      (node (ref "R27") (pin "2") (pinfunction "2_2") (pintype "passive"))
      (node (ref "U5") (pin "1") (pinfunction "SD0_1") (pintype "bidirectional"))
      (node (ref "U7") (pin "8") (pinfunction "SDA_8") (pintype "bidirectional"))
    )
    (net (code "75") (name "POT_SDA_1") (class "Default")
      (node (ref "R31") (pin "2") (pinfunction "2_2") (pintype "passive"))
      (node (ref "U18") (pin "8") (pinfunction "SDA_8") (pintype "bidirectional"))
      (node (ref "U5") (pin "3") (pinfunction "SD1_3") (pintype "bidirectional"))
    )
    (net (code "76") (name "POT_SDA_2") (class "Default")
      (node (ref "R48") (pin "2") (pinfunction "2_2") (pintype "passive"))
      (node (ref "U21") (pin "8") (pinfunction "SDA_8") (pintype "bidirectional"))
      (node (ref "U5") (pin "5") (pinfunction "SD2_5") (pintype "bidirectional"))
    )
    (net (code "77") (name "POT_SDA_3") (class "Default")
      (node (ref "R50") (pin "2") (pinfunction "2_2") (pintype "passive"))
      (node (ref "U24") (pin "8") (pinfunction "SDA_8") (pintype "bidirectional"))
      (node (ref "U5") (pin "7") (pinfunction "SD3_7") (pintype "bidirectional"))
    )
    (net (code "78") (name "POT_~{RESET_0}") (class "Default")
      (node (ref "R18") (pin "2") (pinfunction "2_2") (pintype "passive"))
      (node (ref "U7") (pin "7") (pinfunction "~{RESET}_7") (pintype "bidirectional"))
    )
    (net (code "79") (name "POT_~{RESET_1}") (class "Default")
      (node (ref "R35") (pin "2") (pinfunction "2_2") (pintype "passive"))
      (node (ref "U18") (pin "7") (pinfunction "~{RESET}_7") (pintype "bidirectional"))
    )
    (net (code "80") (name "POT_~{RESET_2}") (class "Default")
      (node (ref "R40") (pin "2") (pinfunction "2_2") (pintype "passive"))
      (node (ref "U21") (pin "7") (pinfunction "~{RESET}_7") (pintype "bidirectional"))
    )
    (net (code "81") (name "POT_~{RESET_3}") (class "Default")
      (node (ref "R45") (pin "2") (pinfunction "2_2") (pintype "passive"))
      (node (ref "U24") (pin "7") (pinfunction "~{RESET}_7") (pintype "bidirectional"))
    )
    (net (code "82") (name "RPI_RX_~{TEROS_TX}") (class "Default")
      (node (ref "JP2") (pin "10") (pinfunction "10_10") (pintype "passive"))
      (node (ref "U14") (pin "4") (pinfunction "2Y_4") (pintype "output"))
    )
    (net (code "83") (name "RPI_TX_~{TEROS_RX}") (class "Default")
      (node (ref "JP2") (pin "8") (pinfunction "8_8") (pintype "passive"))
      (node (ref "U14") (pin "1") (pinfunction "1A_1") (pintype "input"))
    )
    (net (code "84") (name "TEROS_DATA") (class "Default")
      (node (ref "J3") (pin "3") (pinfunction "3_3") (pintype "passive"))
      (node (ref "R28") (pin "2") (pinfunction "2_2") (pintype "passive"))
      (node (ref "R29") (pin "2") (pinfunction "2_2") (pintype "passive"))
      (node (ref "U13") (pin "3") (pinfunction "A_3") (pintype "passive"))
    )
    (net (code "85") (name "TEROS_RX_EN") (class "Default")
      (node (ref "JP2") (pin "11") (pinfunction "11_11") (pintype "passive"))
      (node (ref "U13") (pin "5") (pinfunction "OE_5") (pintype "passive"))
    )
    (net (code "86") (name "TEROS_TX_EN") (class "Default")
      (node (ref "JP2") (pin "7") (pinfunction "7_7") (pintype "passive"))
      (node (ref "U12") (pin "5") (pinfunction "OE_5") (pintype "passive"))
    )
    (net (code "87") (name "VBAT") (class "Default")
      (node (ref "C2") (pin "1") (pinfunction "1_1") (pintype "passive"))
      (node (ref "J1") (pin "2") (pinfunction "+_2") (pintype "bidirectional"))
      (node (ref "Q1") (pin "3") (pinfunction "D_3") (pintype "passive"))
      (node (ref "U2") (pin "3") (pinfunction "VBAT_3") (pintype "power_in"))
    )
    (net (code "88") (name "VCC") (class "Default")
      (node (ref "C10") (pin "1") (pinfunction "1_1") (pintype "passive"))
      (node (ref "C12") (pin "1") (pinfunction "1_1") (pintype "passive"))
      (node (ref "C13") (pin "1") (pinfunction "1_1") (pintype "passive"))
      (node (ref "C14") (pin "1") (pinfunction "1_1") (pintype "passive"))
      (node (ref "C19") (pin "1") (pinfunction "1_1") (pintype "passive"))
      (node (ref "C20") (pin "1") (pinfunction "1_1") (pintype "passive"))
      (node (ref "C24") (pin "1") (pinfunction "1_1") (pintype "passive"))
      (node (ref "C25") (pin "1") (pinfunction "1_1") (pintype "passive"))
      (node (ref "C27") (pin "1") (pinfunction "1_1") (pintype "passive"))
      (node (ref "C33") (pin "1") (pinfunction "1_1") (pintype "passive"))
      (node (ref "C36") (pin "1") (pinfunction "1_1") (pintype "passive"))
      (node (ref "C38") (pin "1") (pinfunction "1_1") (pintype "passive"))
      (node (ref "C39") (pin "1") (pinfunction "1_1") (pintype "passive"))
      (node (ref "C4") (pin "1") (pinfunction "1_1") (pintype "passive"))
      (node (ref "C47") (pin "1") (pinfunction "1_1") (pintype "passive"))
      (node (ref "C48") (pin "1") (pinfunction "1_1") (pintype "passive"))
      (node (ref "C49") (pin "1") (pinfunction "1_1") (pintype "passive"))
      (node (ref "C5") (pin "1") (pinfunction "1_1") (pintype "passive"))
      (node (ref "C50") (pin "1") (pinfunction "1_1") (pintype "passive"))
      (node (ref "C51") (pin "1") (pinfunction "1_1") (pintype "passive"))
      (node (ref "C54") (pin "1") (pinfunction "1_1") (pintype "passive"))
      (node (ref "C55") (pin "1") (pinfunction "1_1") (pintype "passive"))
      (node (ref "C56") (pin "1") (pinfunction "1_1") (pintype "passive"))
      (node (ref "C57") (pin "1") (pinfunction "1_1") (pintype "passive"))
      (node (ref "C58") (pin "1") (pinfunction "1_1") (pintype "passive"))
      (node (ref "C6") (pin "1") (pinfunction "1_1") (pintype "passive"))
      (node (ref "C61") (pin "1") (pinfunction "1_1") (pintype "passive"))
      (node (ref "C62") (pin "1") (pinfunction "1_1") (pintype "passive"))
      (node (ref "C63") (pin "1") (pinfunction "1_1") (pintype "passive"))
      (node (ref "C64") (pin "1") (pinfunction "1_1") (pintype "passive"))
      (node (ref "C65") (pin "1") (pinfunction "1_1") (pintype "passive"))
      (node (ref "C74") (pin "1") (pinfunction "1_1") (pintype "passive"))
      (node (ref "C81") (pin "1") (pinfunction "1_1") (pintype "passive"))
      (node (ref "C82") (pin "1") (pinfunction "1_1") (pintype "passive"))
      (node (ref "C9") (pin "1") (pinfunction "1_1") (pintype "passive"))
      (node (ref "J9") (pin "2") (pinfunction "2_2") (pintype "passive"))
      (node (ref "R12") (pin "1") (pinfunction "1_1") (pintype "passive"))
      (node (ref "R18") (pin "1") (pinfunction "1_1") (pintype "passive"))
      (node (ref "R21") (pin "1") (pinfunction "1_1") (pintype "passive"))
      (node (ref "R23") (pin "1") (pinfunction "1_1") (pintype "passive"))
      (node (ref "R25") (pin "1") (pinfunction "1_1") (pintype "passive"))
      (node (ref "R26") (pin "1") (pinfunction "1_1") (pintype "passive"))
      (node (ref "R27") (pin "1") (pinfunction "1_1") (pintype "passive"))
      (node (ref "R30") (pin "1") (pinfunction "1_1") (pintype "passive"))
      (node (ref "R31") (pin "1") (pinfunction "1_1") (pintype "passive"))
      (node (ref "R32") (pin "1") (pinfunction "1_1") (pintype "passive"))
      (node (ref "R35") (pin "1") (pinfunction "1_1") (pintype "passive"))
      (node (ref "R36") (pin "1") (pinfunction "1_1") (pintype "passive"))
      (node (ref "R37") (pin "1") (pinfunction "1_1") (pintype "passive"))
      (node (ref "R40") (pin "1") (pinfunction "1_1") (pintype "passive"))
      (node (ref "R41") (pin "1") (pinfunction "1_1") (pintype "passive"))
      (node (ref "R42") (pin "1") (pinfunction "1_1") (pintype "passive"))
      (node (ref "R45") (pin "1") (pinfunction "1_1") (pintype "passive"))
      (node (ref "R46") (pin "1") (pinfunction "1_1") (pintype "passive"))
      (node (ref "R47") (pin "1") (pinfunction "1_1") (pintype "passive"))
      (node (ref "R48") (pin "1") (pinfunction "1_1") (pintype "passive"))
      (node (ref "R49") (pin "1") (pinfunction "1_1") (pintype "passive"))
      (node (ref "R50") (pin "1") (pinfunction "1_1") (pintype "passive"))
      (node (ref "R51") (pin "1") (pinfunction "1_1") (pintype "passive"))
      (node (ref "R56") (pin "1") (pinfunction "1_1") (pintype "passive"))
      (node (ref "R61") (pin "1") (pinfunction "1_1") (pintype "passive"))
      (node (ref "R7") (pin "1") (pinfunction "1_1") (pintype "passive"))
      (node (ref "R9") (pin "1") (pinfunction "1_1") (pintype "passive"))
      (node (ref "U1") (pin "6") (pinfunction "VS_6") (pintype "bidirectional"))
      (node (ref "U11") (pin "4") (pinfunction "VDD_4") (pintype "bidirectional"))
      (node (ref "U12") (pin "1") (pinfunction "VCCA_1") (pintype "power_in"))
      (node (ref "U13") (pin "6") (pinfunction "VCCB_6") (pintype "power_in"))
      (node (ref "U14") (pin "5") (pinfunction "VCC_5") (pintype "power_in"))
      (node (ref "U15") (pin "4") (pinfunction "VDD_4") (pintype "bidirectional"))
      (node (ref "U16") (pin "6") (pinfunction "VS_6") (pintype "bidirectional"))
      (node (ref "U17") (pin "2") (pinfunction "VDD_2") (pintype "bidirectional"))
      (node (ref "U17") (pin "3") (pinfunction "S1_3") (pintype "bidirectional"))
      (node (ref "U18") (pin "1") (pinfunction "VDD_1") (pintype "bidirectional"))
      (node (ref "U19") (pin "6") (pinfunction "VS_6") (pintype "bidirectional"))
      (node (ref "U20") (pin "2") (pinfunction "VDD_2") (pintype "bidirectional"))
      (node (ref "U20") (pin "3") (pinfunction "S1_3") (pintype "bidirectional"))
      (node (ref "U21") (pin "1") (pinfunction "VDD_1") (pintype "bidirectional"))
      (node (ref "U22") (pin "6") (pinfunction "VS_6") (pintype "bidirectional"))
      (node (ref "U23") (pin "2") (pinfunction "VDD_2") (pintype "bidirectional"))
      (node (ref "U23") (pin "3") (pinfunction "S1_3") (pintype "bidirectional"))
      (node (ref "U24") (pin "1") (pinfunction "VDD_1") (pintype "bidirectional"))
      (node (ref "U25") (pin "20") (pinfunction "DVDD_20") (pintype "bidirectional"))
      (node (ref "U25") (pin "4") (pinfunction "REFIN+_4") (pintype "bidirectional"))
      (node (ref "U3") (pin "5") (pinfunction "VOUT_5") (pintype "bidirectional"))
      (node (ref "U4") (pin "4") (pinfunction "VDD_4") (pintype "bidirectional"))
      (node (ref "U5") (pin "21") (pinfunction "VCC_21") (pintype "power_in"))
      (node (ref "U6") (pin "2") (pinfunction "VDD_2") (pintype "bidirectional"))
      (node (ref "U6") (pin "3") (pinfunction "S1_3") (pintype "bidirectional"))
      (node (ref "U7") (pin "1") (pinfunction "VDD_1") (pintype "bidirectional"))
      (node (ref "U8") (pin "20") (pinfunction "DVDD_20") (pintype "bidirectional"))
      (node (ref "U8") (pin "4") (pinfunction "REFIN+_4") (pintype "bidirectional"))
    )
    (net (code "89") (name "VCC{slash}2") (class "Default")
      (node (ref "C16") (pin "2") (pinfunction "2_2") (pintype "passive"))
      (node (ref "C17") (pin "2") (pinfunction "2_2") (pintype "passive"))
      (node (ref "C26") (pin "1") (pinfunction "1_1") (pintype "passive"))
      (node (ref "C29") (pin "2") (pinfunction "2_2") (pintype "passive"))
      (node (ref "C30") (pin "2") (pinfunction "2_2") (pintype "passive"))
      (node (ref "C33") (pin "2") (pinfunction "2_2") (pintype "passive"))
      (node (ref "C34") (pin "1") (pinfunction "1_1") (pintype "passive"))
      (node (ref "C5") (pin "2") (pinfunction "2_2") (pintype "passive"))
      (node (ref "C74") (pin "2") (pinfunction "2_2") (pintype "passive"))
      (node (ref "C76") (pin "2") (pinfunction "2_2") (pintype "passive"))
      (node (ref "C77") (pin "2") (pinfunction "2_2") (pintype "passive"))
      (node (ref "C8") (pin "1") (pinfunction "1_1") (pintype "passive"))
      (node (ref "C83") (pin "1") (pinfunction "1_1") (pintype "passive"))
      (node (ref "C85") (pin "2") (pinfunction "2_2") (pintype "passive"))
      (node (ref "C86") (pin "2") (pinfunction "2_2") (pintype "passive"))
      (node (ref "C9") (pin "2") (pinfunction "2_2") (pintype "passive"))
      (node (ref "R11") (pin "2") (pinfunction "2_2") (pintype "passive"))
      (node (ref "R13") (pin "1") (pinfunction "1_1") (pintype "passive"))
      (node (ref "R33") (pin "2") (pinfunction "2_2") (pintype "passive"))
      (node (ref "R34") (pin "1") (pinfunction "1_1") (pintype "passive"))
      (node (ref "R38") (pin "2") (pinfunction "2_2") (pintype "passive"))
      (node (ref "R39") (pin "1") (pinfunction "1_1") (pintype "passive"))
      (node (ref "R43") (pin "2") (pinfunction "2_2") (pintype "passive"))
      (node (ref "R44") (pin "1") (pinfunction "1_1") (pintype "passive"))
      (node (ref "U1") (pin "3") (pinfunction "IN+_3") (pintype "bidirectional"))
      (node (ref "U11") (pin "1") (pinfunction "P$1_1") (pintype "bidirectional"))
      (node (ref "U11") (pin "10") (pinfunction "P$10_10") (pintype "bidirectional"))
      (node (ref "U11") (pin "12") (pinfunction "P$12_12") (pintype "bidirectional"))
      (node (ref "U11") (pin "2") (pinfunction "P$2_2") (pintype "bidirectional"))
      (node (ref "U11") (pin "5") (pinfunction "P$5_5") (pintype "bidirectional"))
      (node (ref "U16") (pin "3") (pinfunction "IN+_3") (pintype "bidirectional"))
      (node (ref "U18") (pin "3") (pinfunction "W_3") (pintype "bidirectional"))
      (node (ref "U19") (pin "3") (pinfunction "IN+_3") (pintype "bidirectional"))
      (node (ref "U21") (pin "3") (pinfunction "W_3") (pintype "bidirectional"))
      (node (ref "U22") (pin "3") (pinfunction "IN+_3") (pintype "bidirectional"))
      (node (ref "U24") (pin "3") (pinfunction "W_3") (pintype "bidirectional"))
      (node (ref "U25") (pin "10") (pinfunction "CH5_10") (pintype "bidirectional"))
      (node (ref "U25") (pin "12") (pinfunction "CH7_12") (pintype "bidirectional"))
      (node (ref "U25") (pin "6") (pinfunction "CH1_6") (pintype "bidirectional"))
      (node (ref "U25") (pin "8") (pinfunction "CH3_8") (pintype "bidirectional"))
      (node (ref "U7") (pin "3") (pinfunction "W_3") (pintype "bidirectional"))
      (node (ref "U8") (pin "10") (pinfunction "CH5_10") (pintype "bidirectional"))
      (node (ref "U8") (pin "12") (pinfunction "CH7_12") (pintype "bidirectional"))
      (node (ref "U8") (pin "6") (pinfunction "CH1_6") (pintype "bidirectional"))
      (node (ref "U8") (pin "8") (pinfunction "CH3_8") (pintype "bidirectional"))
    )
    (net (code "90") (name "VCC{slash}2_UNBUFFERED") (class "Default")
      (node (ref "C6") (pin "2") (pinfunction "2_2") (pintype "passive"))
      (node (ref "C7") (pin "1") (pinfunction "1_1") (pintype "passive"))
      (node (ref "R10") (pin "1") (pinfunction "1_1") (pintype "passive"))
      (node (ref "R9") (pin "2") (pinfunction "2_2") (pintype "passive"))
      (node (ref "U11") (pin "3") (pinfunction "P$3_3") (pintype "bidirectional"))
    )
    (net (code "91") (name "VOC_DISCONNECT_0") (class "Default")
      (node (ref "JP2") (pin "22") (pinfunction "22_22") (pintype "passive"))
      (node (ref "R25") (pin "2") (pinfunction "2_2") (pintype "passive"))
      (node (ref "U6") (pin "6") (pinfunction "SEL_6") (pintype "bidirectional"))
    )
    (net (code "92") (name "VOC_DISCONNECT_1") (class "Default")
      (node (ref "JP2") (pin "29") (pinfunction "29_29") (pintype "passive"))
      (node (ref "R37") (pin "2") (pinfunction "2_2") (pintype "passive"))
      (node (ref "U17") (pin "6") (pinfunction "SEL_6") (pintype "bidirectional"))
    )
    (net (code "93") (name "VOC_DISCONNECT_2") (class "Default")
      (node (ref "JP2") (pin "18") (pinfunction "18_18") (pintype "passive"))
      (node (ref "R42") (pin "2") (pinfunction "2_2") (pintype "passive"))
      (node (ref "U20") (pin "6") (pinfunction "SEL_6") (pintype "bidirectional"))
    )
    (net (code "94") (name "VOC_DISCONNECT_3") (class "Default")
      (node (ref "JP2") (pin "16") (pinfunction "16_16") (pintype "passive"))
      (node (ref "R47") (pin "2") (pinfunction "2_2") (pintype "passive"))
      (node (ref "U23") (pin "6") (pinfunction "SEL_6") (pintype "bidirectional"))
    )
    (net (code "95") (name "VSENSE_LPF_0") (class "Default")
      (node (ref "C18") (pin "1") (pinfunction "1_1") (pintype "passive"))
      (node (ref "U4") (pin "1") (pinfunction "P$1_1") (pintype "bidirectional"))
      (node (ref "U4") (pin "2") (pinfunction "P$2_2") (pintype "bidirectional"))
      (node (ref "U8") (pin "7") (pinfunction "CH2_7") (pintype "bidirectional"))
    )
    (net (code "96") (name "VSENSE_LPF_1") (class "Default")
      (node (ref "C31") (pin "1") (pinfunction "1_1") (pintype "passive"))
      (node (ref "U4") (pin "6") (pinfunction "P$6_6") (pintype "bidirectional"))
      (node (ref "U4") (pin "7") (pinfunction "P$7_7") (pintype "bidirectional"))
      (node (ref "U8") (pin "11") (pinfunction "CH6_11") (pintype "bidirectional"))
    )
    (net (code "97") (name "VSENSE_LPF_2") (class "Default")
      (node (ref "C78") (pin "1") (pinfunction "1_1") (pintype "passive"))
      (node (ref "U15") (pin "1") (pinfunction "P$1_1") (pintype "bidirectional"))
      (node (ref "U15") (pin "2") (pinfunction "P$2_2") (pintype "bidirectional"))
      (node (ref "U25") (pin "7") (pinfunction "CH2_7") (pintype "bidirectional"))
    )
    (net (code "98") (name "VSENSE_LPF_3") (class "Default")
      (node (ref "C87") (pin "1") (pinfunction "1_1") (pintype "passive"))
      (node (ref "U15") (pin "6") (pinfunction "P$6_6") (pintype "bidirectional"))
      (node (ref "U15") (pin "7") (pinfunction "P$7_7") (pintype "bidirectional"))
      (node (ref "U25") (pin "11") (pinfunction "CH6_11") (pintype "bidirectional"))
    )
    (net (code "99") (name "VSENSE_V+_0") (class "Default")
      (node (ref "C17") (pin "1") (pinfunction "1_1") (pintype "passive"))
      (node (ref "R17") (pin "2") (pinfunction "2_2") (pintype "passive"))
      (node (ref "U4") (pin "3") (pinfunction "P$3_3") (pintype "bidirectional"))
    )
    (net (code "100") (name "VSENSE_V+_1") (class "Default")
      (node (ref "C30") (pin "1") (pinfunction "1_1") (pintype "passive"))
      (node (ref "R24") (pin "2") (pinfunction "2_2") (pintype "passive"))
      (node (ref "U4") (pin "5") (pinfunction "P$5_5") (pintype "bidirectional"))
    )
    (net (code "101") (name "VSENSE_V+_2") (class "Default")
      (node (ref "C77") (pin "1") (pinfunction "1_1") (pintype "passive"))
      (node (ref "R55") (pin "2") (pinfunction "2_2") (pintype "passive"))
      (node (ref "U15") (pin "3") (pinfunction "P$3_3") (pintype "bidirectional"))
    )
    (net (code "102") (name "VSENSE_V+_3") (class "Default")
      (node (ref "C86") (pin "1") (pinfunction "1_1") (pintype "passive"))
      (node (ref "R60") (pin "2") (pinfunction "2_2") (pintype "passive"))
      (node (ref "U15") (pin "5") (pinfunction "P$5_5") (pintype "bidirectional"))
    )
    (net (code "103") (name "VSYS") (class "Default")
      (node (ref "C3") (pin "1") (pinfunction "1_1") (pintype "passive"))
      (node (ref "C35") (pin "1") (pinfunction "1_1") (pintype "passive"))
      (node (ref "C37") (pin "1") (pinfunction "1_1") (pintype "passive"))
      (node (ref "J3") (pin "2") (pinfunction "2_2") (pintype "passive"))
      (node (ref "Q1") (pin "2") (pinfunction "S_2") (pintype "passive"))
      (node (ref "Q2") (pin "1") (pinfunction "G_1") (pintype "passive"))
      (node (ref "Q2") (pin "2") (pinfunction "S_2") (pintype "passive"))
      (node (ref "R1") (pin "2") (pinfunction "2_2") (pintype "passive"))
      (node (ref "U12") (pin "6") (pinfunction "VCCB_6") (pintype "power_in"))
      (node (ref "U13") (pin "1") (pinfunction "VCCA_1") (pintype "power_in"))
      (node (ref "U3") (pin "1") (pinfunction "VIN_1") (pintype "bidirectional"))
      (node (ref "U3") (pin "3") (pinfunction "EN_3") (pintype "bidirectional"))
    )
    (net (code "104") (name "VUSB") (class "Default")
      (node (ref "J2") (pin "A4B9") (pinfunction "VBUS_A4B9") (pintype "bidirectional"))
      (node (ref "J2") (pin "B4A9") (pinfunction "VBUS_B4A9") (pintype "bidirectional"))
      (node (ref "JP1") (pin "2") (pinfunction "2_2") (pintype "passive"))
    )
    (net (code "105") (name "unconnected-(J1-PAD1-PadNC1)") (class "Default")
      (node (ref "J1") (pin "NC1") (pinfunction "PAD1_NC1") (pintype "bidirectional"))
    )
    (net (code "106") (name "unconnected-(J1-PAD2-PadNC2)") (class "Default")
      (node (ref "J1") (pin "NC2") (pinfunction "PAD2_NC2") (pintype "bidirectional"))
    )
    (net (code "107") (name "unconnected-(J2-SBU1-PadA8)") (class "Default")
      (node (ref "J2") (pin "A8") (pinfunction "SBU1_A8") (pintype "bidirectional"))
    )
    (net (code "108") (name "unconnected-(J2-SBU2-PadB8)") (class "Default")
      (node (ref "J2") (pin "B8") (pinfunction "SBU2_B8") (pintype "bidirectional"))
    )
    (net (code "109") (name "unconnected-(JP2-Pad1)") (class "Default")
      (node (ref "JP2") (pin "1") (pinfunction "1_1") (pintype "passive"))
    )
    (net (code "110") (name "unconnected-(JP2-Pad12)") (class "Default")
      (node (ref "JP2") (pin "12") (pinfunction "12_12") (pintype "passive"))
    )
    (net (code "111") (name "unconnected-(JP2-Pad13)") (class "Default")
      (node (ref "JP2") (pin "13") (pinfunction "13_13") (pintype "passive"))
    )
    (net (code "112") (name "unconnected-(JP2-Pad15)") (class "Default")
      (node (ref "JP2") (pin "15") (pinfunction "15_15") (pintype "passive"))
    )
    (net (code "113") (name "unconnected-(JP2-Pad17)") (class "Default")
      (node (ref "JP2") (pin "17") (pinfunction "17_17") (pintype "passive"))
    )
    (net (code "114") (name "unconnected-(JP2-Pad27)") (class "Default")
      (node (ref "JP2") (pin "27") (pinfunction "27_27") (pintype "passive"))
    )
    (net (code "115") (name "unconnected-(JP2-Pad28)") (class "Default")
      (node (ref "JP2") (pin "28") (pinfunction "28_28") (pintype "passive"))
    )
    (net (code "116") (name "unconnected-(JP2-Pad31)") (class "Default")
      (node (ref "JP2") (pin "31") (pinfunction "31_31") (pintype "passive"))
    )
    (net (code "117") (name "unconnected-(JP2-Pad32)") (class "Default")
      (node (ref "JP2") (pin "32") (pinfunction "32_32") (pintype "passive"))
    )
    (net (code "118") (name "unconnected-(JP2-Pad33)") (class "Default")
      (node (ref "JP2") (pin "33") (pinfunction "33_33") (pintype "passive"))
    )
    (net (code "119") (name "unconnected-(JP2-Pad35)") (class "Default")
      (node (ref "JP2") (pin "35") (pinfunction "35_35") (pintype "passive"))
    )
    (net (code "120") (name "unconnected-(JP2-Pad36)") (class "Default")
      (node (ref "JP2") (pin "36") (pinfunction "36_36") (pintype "passive"))
    )
    (net (code "121") (name "unconnected-(JP2-Pad37)") (class "Default")
      (node (ref "JP2") (pin "37") (pinfunction "37_37") (pintype "passive"))
    )
    (net (code "122") (name "unconnected-(JP2-Pad38)") (class "Default")
      (node (ref "JP2") (pin "38") (pinfunction "38_38") (pintype "passive"))
    )
    (net (code "123") (name "unconnected-(JP2-Pad40)") (class "Default")
      (node (ref "JP2") (pin "40") (pinfunction "40_40") (pintype "passive"))
    )
    (net (code "124") (name "unconnected-(U5-SC4-Pad11)") (class "Default")
      (node (ref "U5") (pin "11") (pinfunction "SC4_11") (pintype "bidirectional"))
    )
    (net (code "125") (name "unconnected-(U5-SC5-Pad13)") (class "Default")
      (node (ref "U5") (pin "13") (pinfunction "SC5_13") (pintype "bidirectional"))
    )
    (net (code "126") (name "unconnected-(U5-SC6-Pad15)") (class "Default")
      (node (ref "U5") (pin "15") (pinfunction "SC6_15") (pintype "bidirectional"))
    )
    (net (code "127") (name "unconnected-(U5-SC7-Pad17)") (class "Default")
      (node (ref "U5") (pin "17") (pinfunction "SC7_17") (pintype "bidirectional"))
    )
    (net (code "128") (name "unconnected-(U5-SD4-Pad10)") (class "Default")
      (node (ref "U5") (pin "10") (pinfunction "SD4_10") (pintype "bidirectional"))
    )
    (net (code "129") (name "unconnected-(U5-SD5-Pad12)") (class "Default")
      (node (ref "U5") (pin "12") (pinfunction "SD5_12") (pintype "bidirectional"))
    )
    (net (code "130") (name "unconnected-(U5-SD6-Pad14)") (class "Default")
      (node (ref "U5") (pin "14") (pinfunction "SD6_14") (pintype "bidirectional"))
    )
    (net (code "131") (name "unconnected-(U5-SD7-Pad16)") (class "Default")
      (node (ref "U5") (pin "16") (pinfunction "SD7_16") (pintype "bidirectional"))
    )
    (net (code "132") (name "unconnected-(U8-MCLK-Pad18)") (class "Default")
      (node (ref "U8") (pin "18") (pinfunction "MCLK_18") (pintype "bidirectional"))
    )
    (net (code "133") (name "unconnected-(U8-~{IRQ}{slash}MDAT-Pad17)") (class "Default")
      (node (ref "U8") (pin "17") (pinfunction "~{IRQ}/MDAT_17") (pintype "bidirectional"))
    )
    (net (code "134") (name "unconnected-(U25-MCLK-Pad18)") (class "Default")
      (node (ref "U25") (pin "18") (pinfunction "MCLK_18") (pintype "bidirectional"))
    )
    (net (code "135") (name "unconnected-(U25-~{IRQ}{slash}MDAT-Pad17)") (class "Default")
      (node (ref "U25") (pin "17") (pinfunction "~{IRQ}/MDAT_17") (pintype "bidirectional"))
    )
    (net (code "136") (name "~{RPI_RX}_TEROS_TX") (class "Default")
      (node (ref "U13") (pin "4") (pinfunction "BY_4") (pintype "passive"))
      (node (ref "U14") (pin "3") (pinfunction "2A_3") (pintype "input"))
    )
    (net (code "137") (name "~{RPI_TX}_TEROS_RX") (class "Default")
      (node (ref "U12") (pin "3") (pinfunction "A_3") (pintype "passive"))
      (node (ref "U14") (pin "6") (pinfunction "1Y_6") (pintype "output"))
    )
  )
)
